# 80_LED_WS2812_panels.net
KiCad netlist of a schematic drawn in EAGLE
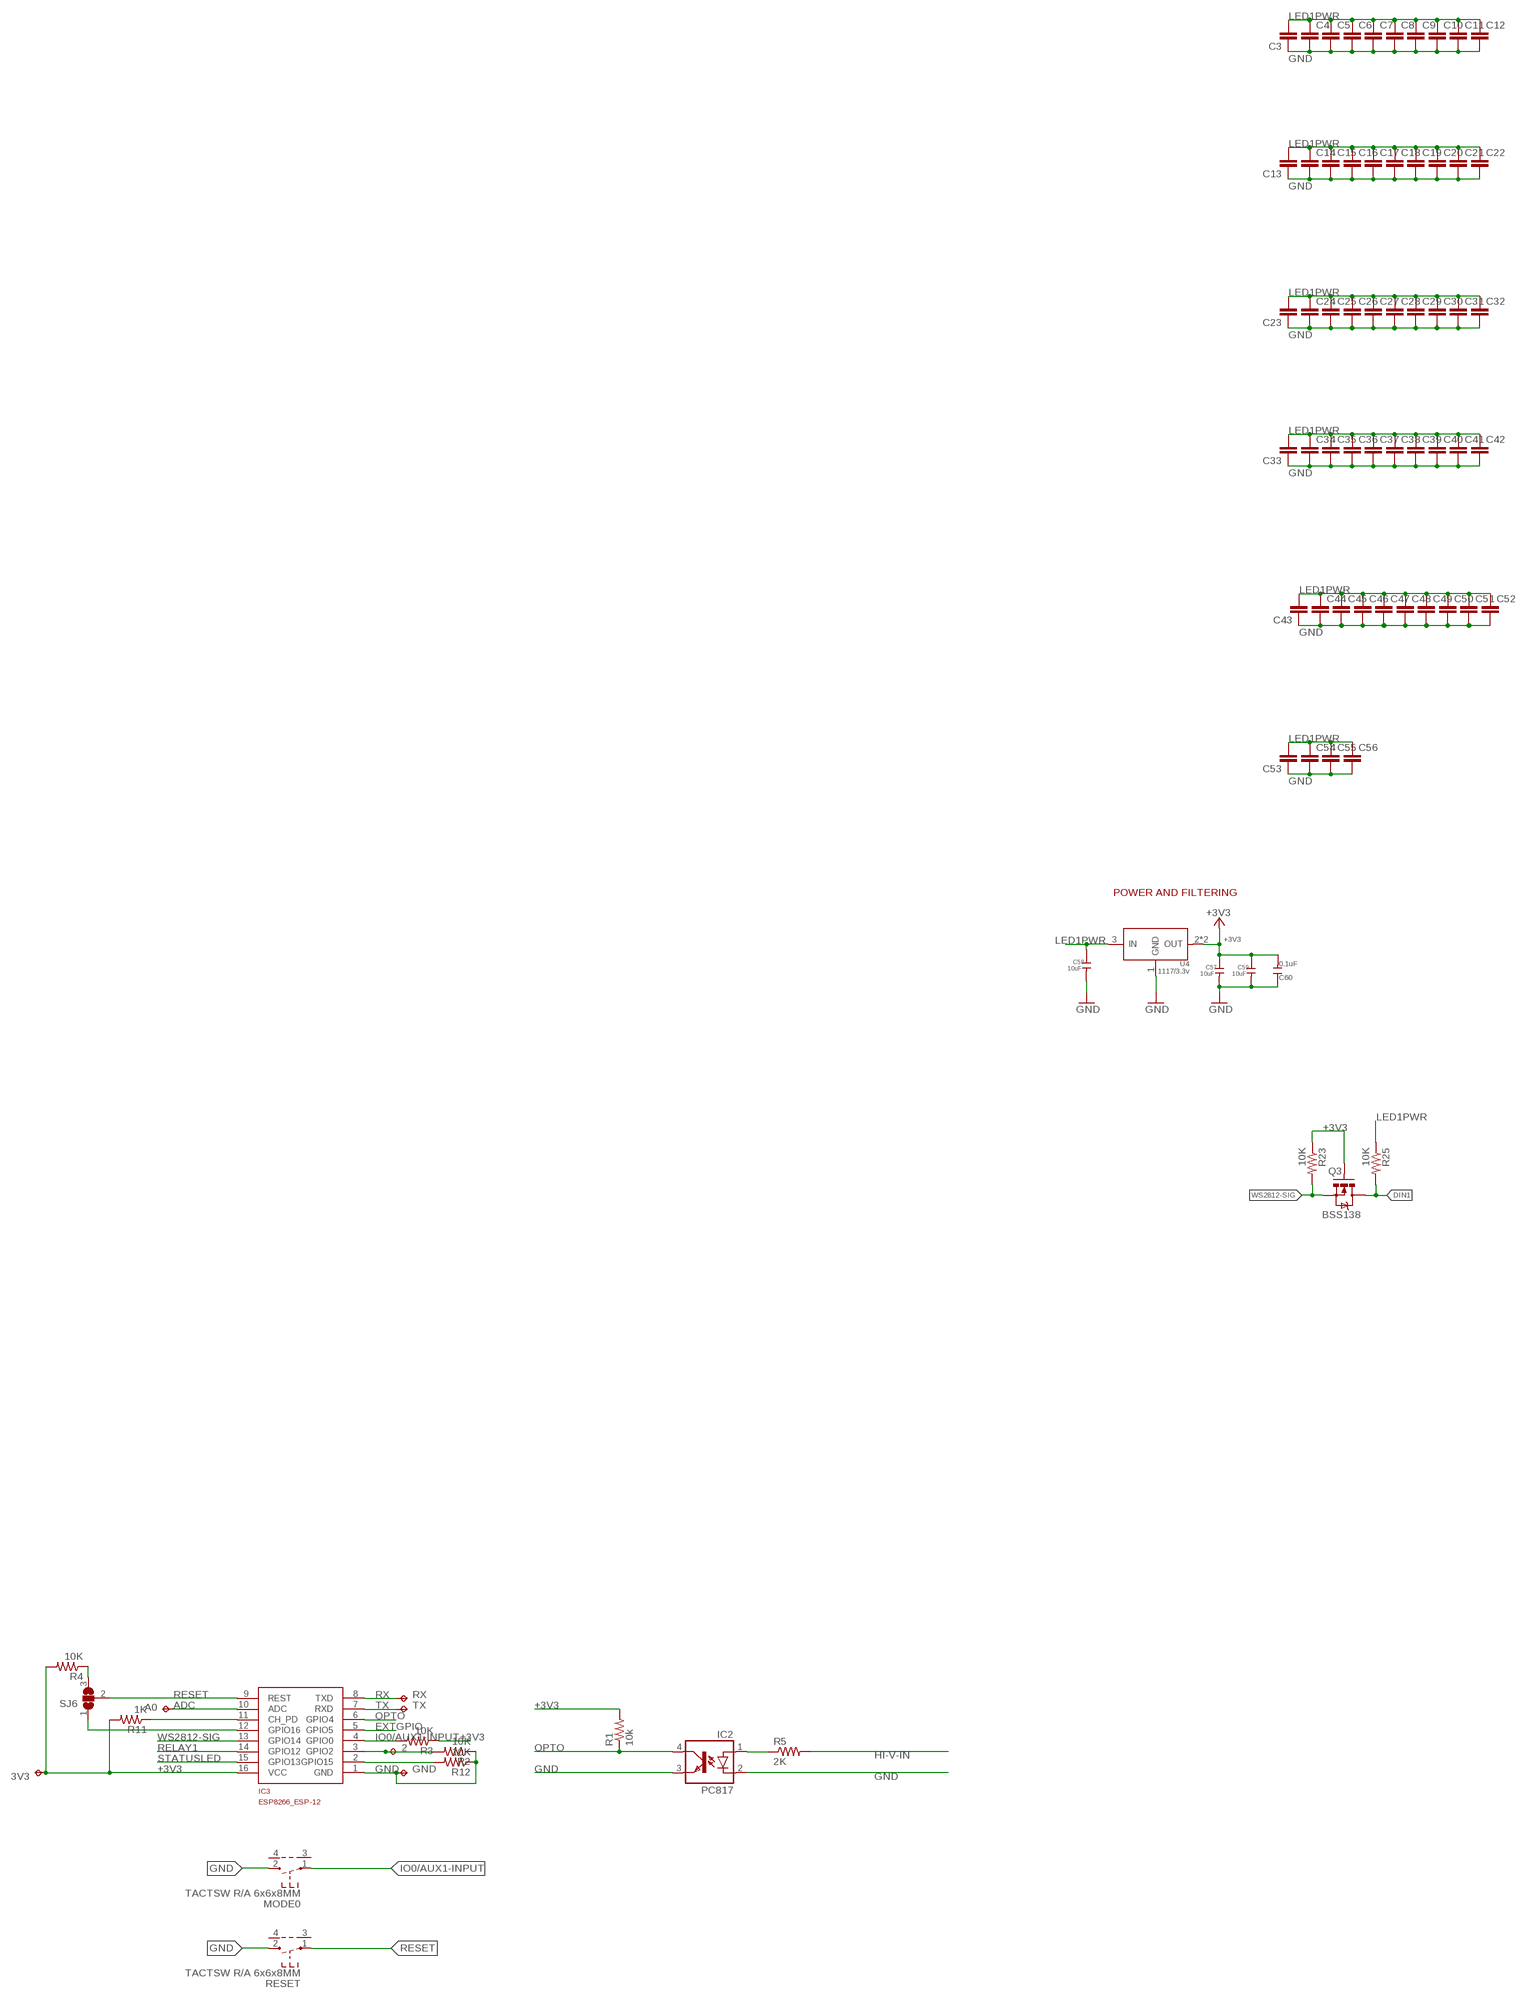
[diagram p0: schematic, sheet 1, part 1 of 2]
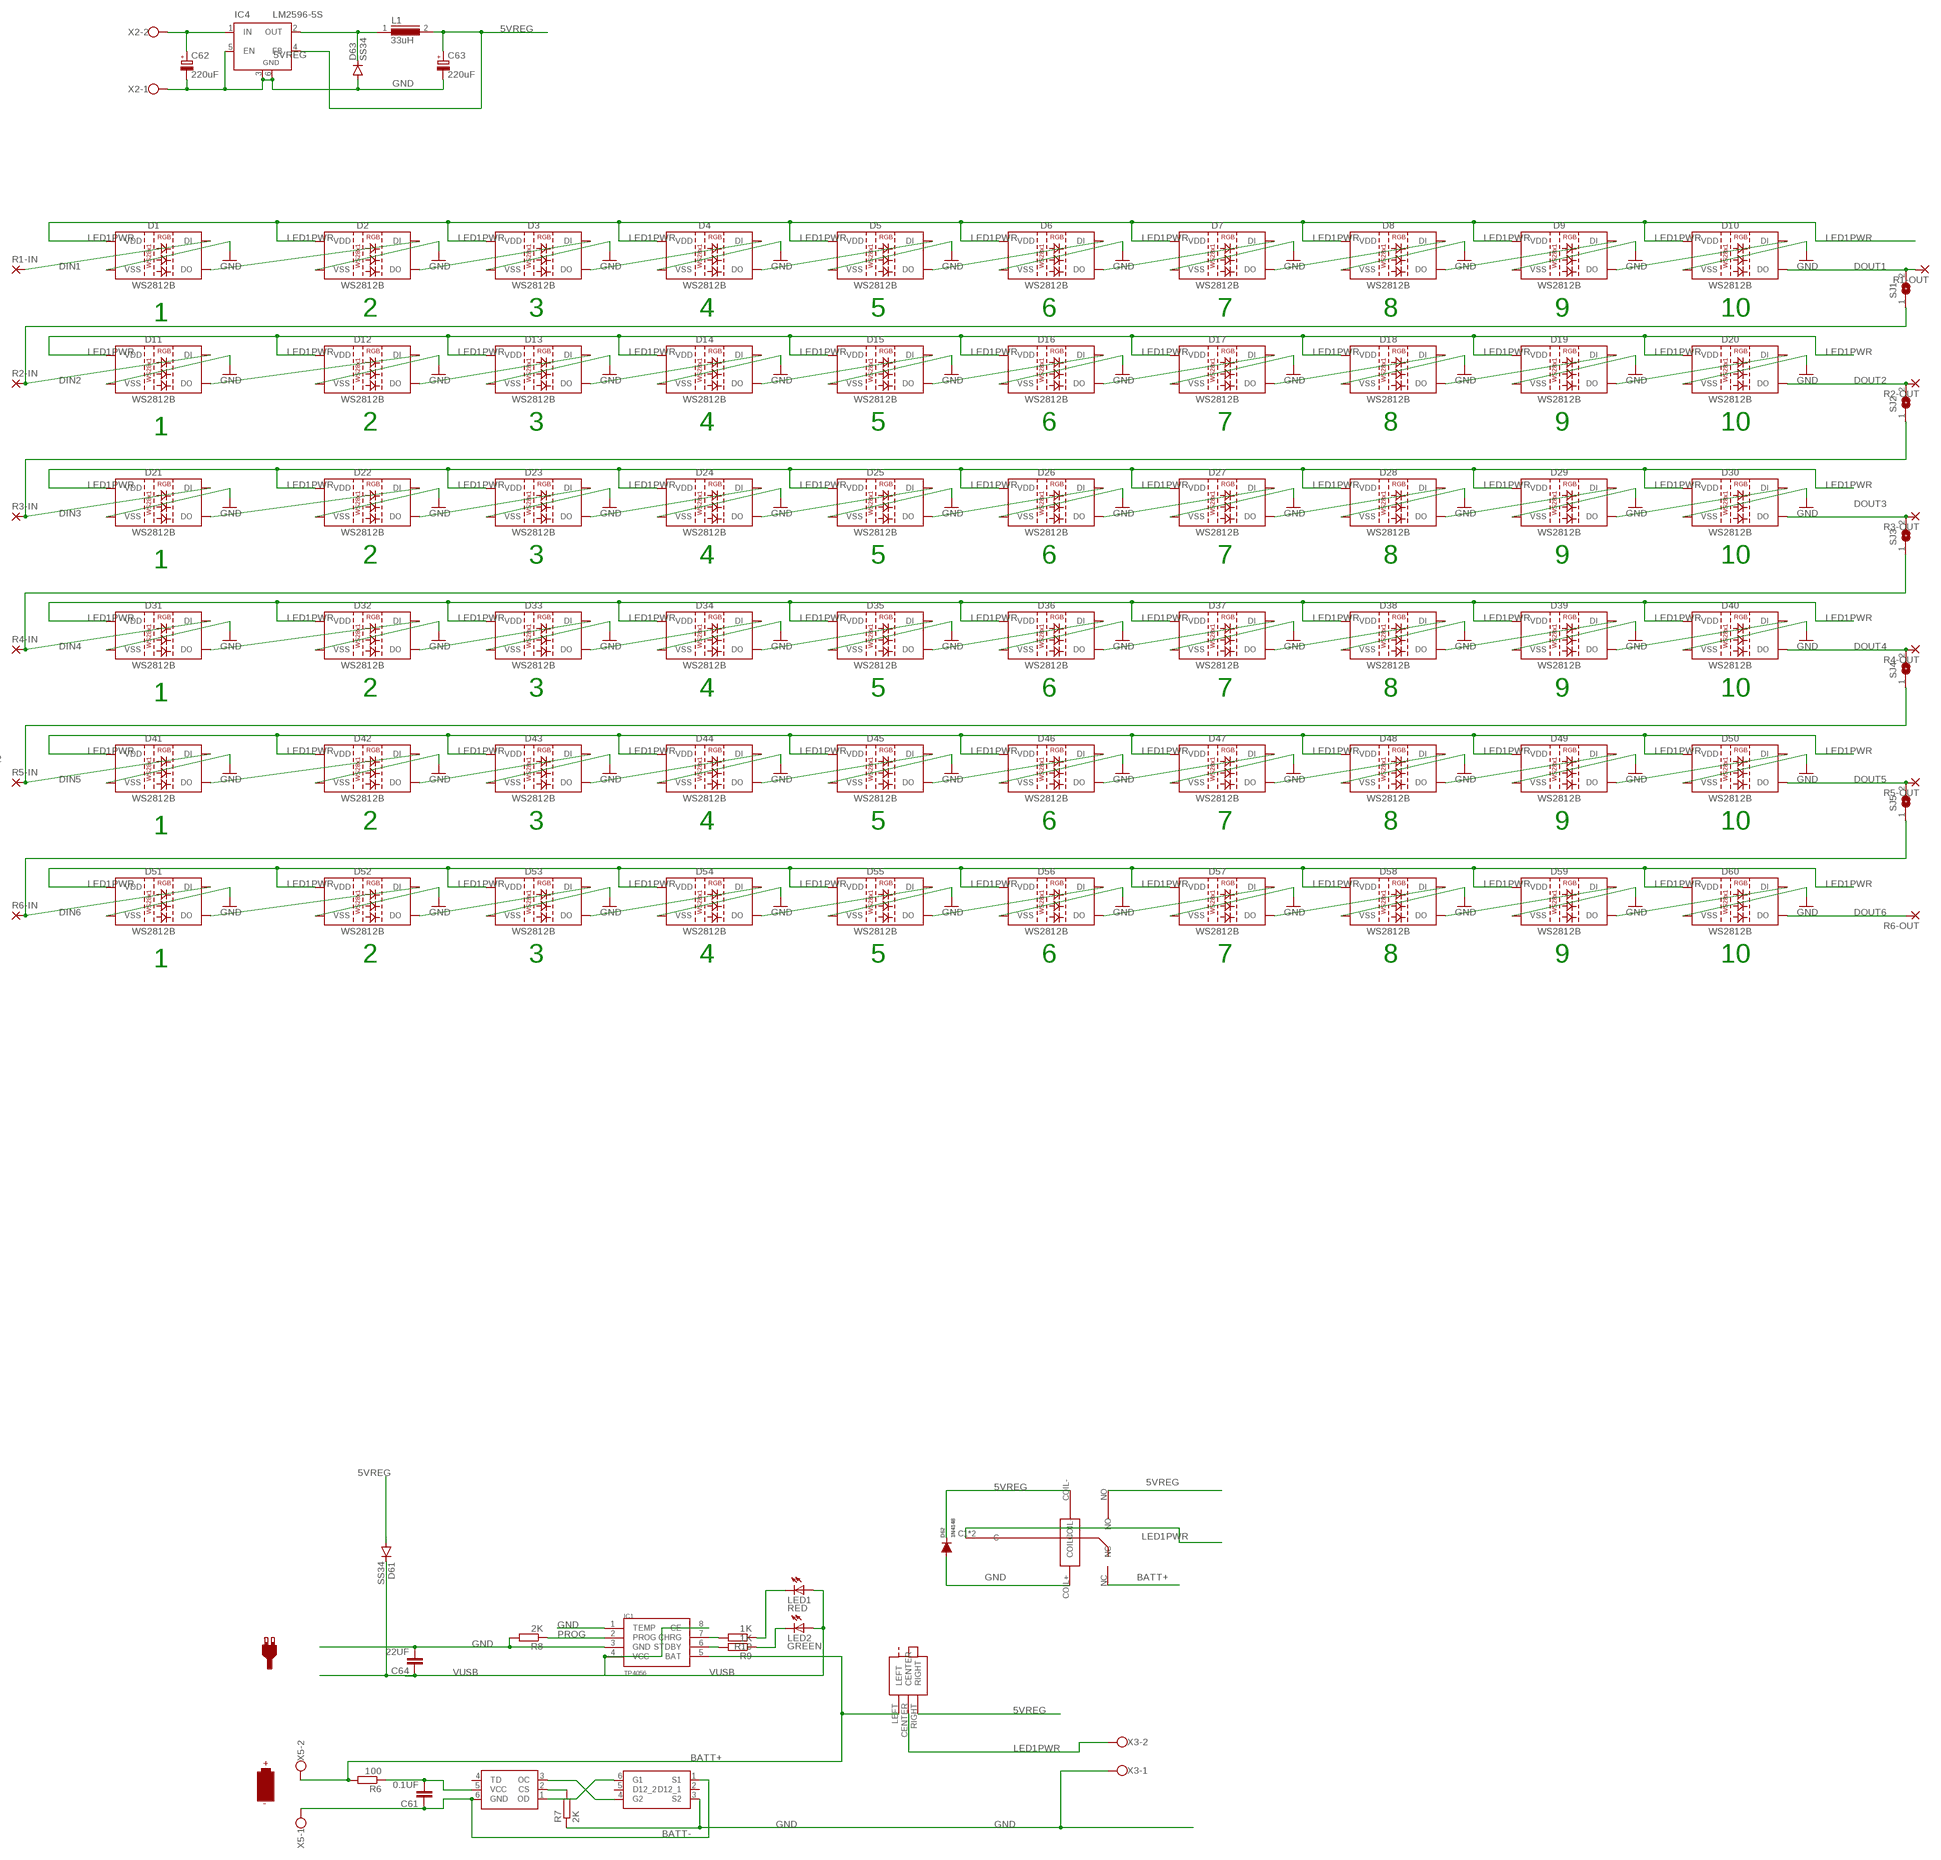
[diagram p1: schematic, sheet 1, part 2 of 2]

(export (version "E")
  (design (tool "Eeschema 10.0.6"))
  (components
    (comp (ref "2")
      (value "TPTP13SQ")
      (footprint "eagle-import:TP13SQ")
      (libsource (lib "eagle-import") (part "TPTP13SQ"))
    )
    (comp (ref "3V3")
      (value "TPTP13SQ")
      (footprint "eagle-import:TP13SQ")
      (libsource (lib "eagle-import") (part "TPTP13SQ"))
    )
    (comp (ref "A0")
      (value "TPTP13SQ")
      (footprint "eagle-import:TP13SQ")
      (libsource (lib "eagle-import") (part "TPTP13SQ"))
    )
    (comp (ref "C3")
      (value "C-EUC1206")
      (footprint "eagle-import:C1206@1")
      (libsource (lib "eagle-import") (part "C-EUC1206"))
    )
    (comp (ref "C4")
      (value "C-EUC1206")
      (footprint "eagle-import:C1206@1")
      (libsource (lib "eagle-import") (part "C-EUC1206"))
    )
    (comp (ref "C5")
      (value "C-EUC1206")
      (footprint "eagle-import:C1206@1")
      (libsource (lib "eagle-import") (part "C-EUC1206"))
    )
    (comp (ref "C6")
      (value "C-EUC1206")
      (footprint "eagle-import:C1206@1")
      (libsource (lib "eagle-import") (part "C-EUC1206"))
    )
    (comp (ref "C7")
      (value "C-EUC1206")
      (footprint "eagle-import:C1206@1")
      (libsource (lib "eagle-import") (part "C-EUC1206"))
    )
    (comp (ref "C8")
      (value "C-EUC1206")
      (footprint "eagle-import:C1206@1")
      (libsource (lib "eagle-import") (part "C-EUC1206"))
    )
    (comp (ref "C9")
      (value "C-EUC1206")
      (footprint "eagle-import:C1206@1")
      (libsource (lib "eagle-import") (part "C-EUC1206"))
    )
    (comp (ref "C10")
      (value "C-EUC1206")
      (footprint "eagle-import:C1206@1")
      (libsource (lib "eagle-import") (part "C-EUC1206"))
    )
    (comp (ref "C11")
      (value "C-EUC1206")
      (footprint "eagle-import:C1206@1")
      (libsource (lib "eagle-import") (part "C-EUC1206"))
    )
    (comp (ref "C12")
      (value "C-EUC1206")
      (footprint "eagle-import:C1206@1")
      (libsource (lib "eagle-import") (part "C-EUC1206"))
    )
    (comp (ref "C13")
      (value "C-EUC1206")
      (footprint "eagle-import:C1206@1")
      (libsource (lib "eagle-import") (part "C-EUC1206"))
    )
    (comp (ref "C14")
      (value "C-EUC1206")
      (footprint "eagle-import:C1206@1")
      (libsource (lib "eagle-import") (part "C-EUC1206"))
    )
    (comp (ref "C15")
      (value "C-EUC1206")
      (footprint "eagle-import:C1206@1")
      (libsource (lib "eagle-import") (part "C-EUC1206"))
    )
    (comp (ref "C16")
      (value "C-EUC1206")
      (footprint "eagle-import:C1206@1")
      (libsource (lib "eagle-import") (part "C-EUC1206"))
    )
    (comp (ref "C17")
      (value "C-EUC1206")
      (footprint "eagle-import:C1206@1")
      (libsource (lib "eagle-import") (part "C-EUC1206"))
    )
    (comp (ref "C18")
      (value "C-EUC1206")
      (footprint "eagle-import:C1206@1")
      (libsource (lib "eagle-import") (part "C-EUC1206"))
    )
    (comp (ref "C19")
      (value "C-EUC1206")
      (footprint "eagle-import:C1206@1")
      (libsource (lib "eagle-import") (part "C-EUC1206"))
    )
    (comp (ref "C20")
      (value "C-EUC1206")
      (footprint "eagle-import:C1206@1")
      (libsource (lib "eagle-import") (part "C-EUC1206"))
    )
    (comp (ref "C21")
      (value "C-EUC1206")
      (footprint "eagle-import:C1206@1")
      (libsource (lib "eagle-import") (part "C-EUC1206"))
    )
    (comp (ref "C22")
      (value "C-EUC1206")
      (footprint "eagle-import:C1206@1")
      (libsource (lib "eagle-import") (part "C-EUC1206"))
    )
    (comp (ref "C23")
      (value "C-EUC1206")
      (footprint "eagle-import:C1206@1")
      (libsource (lib "eagle-import") (part "C-EUC1206"))
    )
    (comp (ref "C24")
      (value "C-EUC1206")
      (footprint "eagle-import:C1206@1")
      (libsource (lib "eagle-import") (part "C-EUC1206"))
    )
    (comp (ref "C25")
      (value "C-EUC1206")
      (footprint "eagle-import:C1206@1")
      (libsource (lib "eagle-import") (part "C-EUC1206"))
    )
    (comp (ref "C26")
      (value "C-EUC1206")
      (footprint "eagle-import:C1206@1")
      (libsource (lib "eagle-import") (part "C-EUC1206"))
    )
    (comp (ref "C27")
      (value "C-EUC1206")
      (footprint "eagle-import:C1206@1")
      (libsource (lib "eagle-import") (part "C-EUC1206"))
    )
    (comp (ref "C28")
      (value "C-EUC1206")
      (footprint "eagle-import:C1206@1")
      (libsource (lib "eagle-import") (part "C-EUC1206"))
    )
    (comp (ref "C29")
      (value "C-EUC1206")
      (footprint "eagle-import:C1206@1")
      (libsource (lib "eagle-import") (part "C-EUC1206"))
    )
    (comp (ref "C30")
      (value "C-EUC1206")
      (footprint "eagle-import:C1206@1")
      (libsource (lib "eagle-import") (part "C-EUC1206"))
    )
    (comp (ref "C31")
      (value "C-EUC1206")
      (footprint "eagle-import:C1206@1")
      (libsource (lib "eagle-import") (part "C-EUC1206"))
    )
    (comp (ref "C32")
      (value "C-EUC1206")
      (footprint "eagle-import:C1206@1")
      (libsource (lib "eagle-import") (part "C-EUC1206"))
    )
    (comp (ref "C33")
      (value "C-EUC1206")
      (footprint "eagle-import:C1206@1")
      (libsource (lib "eagle-import") (part "C-EUC1206"))
    )
    (comp (ref "C34")
      (value "C-EUC1206")
      (footprint "eagle-import:C1206@1")
      (libsource (lib "eagle-import") (part "C-EUC1206"))
    )
    (comp (ref "C35")
      (value "C-EUC1206")
      (footprint "eagle-import:C1206@1")
      (libsource (lib "eagle-import") (part "C-EUC1206"))
    )
    (comp (ref "C36")
      (value "C-EUC1206")
      (footprint "eagle-import:C1206@1")
      (libsource (lib "eagle-import") (part "C-EUC1206"))
    )
    (comp (ref "C37")
      (value "C-EUC1206")
      (footprint "eagle-import:C1206@1")
      (libsource (lib "eagle-import") (part "C-EUC1206"))
    )
    (comp (ref "C38")
      (value "C-EUC1206")
      (footprint "eagle-import:C1206@1")
      (libsource (lib "eagle-import") (part "C-EUC1206"))
    )
    (comp (ref "C39")
      (value "C-EUC1206")
      (footprint "eagle-import:C1206@1")
      (libsource (lib "eagle-import") (part "C-EUC1206"))
    )
    (comp (ref "C40")
      (value "C-EUC1206")
      (footprint "eagle-import:C1206@1")
      (libsource (lib "eagle-import") (part "C-EUC1206"))
    )
    (comp (ref "C41")
      (value "C-EUC1206")
      (footprint "eagle-import:C1206@1")
      (libsource (lib "eagle-import") (part "C-EUC1206"))
    )
    (comp (ref "C42")
      (value "C-EUC1206")
      (footprint "eagle-import:C1206@1")
      (libsource (lib "eagle-import") (part "C-EUC1206"))
    )
    (comp (ref "C43")
      (value "C-EUC1206")
      (footprint "eagle-import:C1206@1")
      (libsource (lib "eagle-import") (part "C-EUC1206"))
    )
    (comp (ref "C44")
      (value "C-EUC1206")
      (footprint "eagle-import:C1206@1")
      (libsource (lib "eagle-import") (part "C-EUC1206"))
    )
    (comp (ref "C45")
      (value "C-EUC1206")
      (footprint "eagle-import:C1206@1")
      (libsource (lib "eagle-import") (part "C-EUC1206"))
    )
    (comp (ref "C46")
      (value "C-EUC1206")
      (footprint "eagle-import:C1206@1")
      (libsource (lib "eagle-import") (part "C-EUC1206"))
    )
    (comp (ref "C47")
      (value "C-EUC1206")
      (footprint "eagle-import:C1206@1")
      (libsource (lib "eagle-import") (part "C-EUC1206"))
    )
    (comp (ref "C48")
      (value "C-EUC1206")
      (footprint "eagle-import:C1206@1")
      (libsource (lib "eagle-import") (part "C-EUC1206"))
    )
    (comp (ref "C49")
      (value "C-EUC1206")
      (footprint "eagle-import:C1206@1")
      (libsource (lib "eagle-import") (part "C-EUC1206"))
    )
    (comp (ref "C50")
      (value "C-EUC1206")
      (footprint "eagle-import:C1206@1")
      (libsource (lib "eagle-import") (part "C-EUC1206"))
    )
    (comp (ref "C51")
      (value "C-EUC1206")
      (footprint "eagle-import:C1206@1")
      (libsource (lib "eagle-import") (part "C-EUC1206"))
    )
    (comp (ref "C52")
      (value "C-EUC1206")
      (footprint "eagle-import:C1206@1")
      (libsource (lib "eagle-import") (part "C-EUC1206"))
    )
    (comp (ref "C53")
      (value "C-EUC1206")
      (footprint "eagle-import:C1206@1")
      (libsource (lib "eagle-import") (part "C-EUC1206"))
    )
    (comp (ref "C54")
      (value "C-EUC1206")
      (footprint "eagle-import:C1206@1")
      (libsource (lib "eagle-import") (part "C-EUC1206"))
    )
    (comp (ref "C55")
      (value "C-EUC1206")
      (footprint "eagle-import:C1206@1")
      (libsource (lib "eagle-import") (part "C-EUC1206"))
    )
    (comp (ref "C56")
      (value "C-EUC1206")
      (footprint "eagle-import:C1206@1")
      (libsource (lib "eagle-import") (part "C-EUC1206"))
    )
    (comp (ref "C57")
      (value "10uF")
      (footprint "eagle-import:C1206")
      (libsource (lib "eagle-import") (part "C-1206"))
    )
    (comp (ref "C58")
      (value "10uF")
      (footprint "eagle-import:C1206")
      (libsource (lib "eagle-import") (part "C-1206"))
    )
    (comp (ref "C59")
      (value "10uF")
      (footprint "eagle-import:C1206")
      (libsource (lib "eagle-import") (part "C-1206"))
    )
    (comp (ref "C60")
      (value "0.1uF")
      (footprint "eagle-import:DISCRETE_C1206")
      (libsource (lib "eagle-import") (part "DISCRETE_C-1206"))
    )
    (comp (ref "C61")
      (value "0.1UF")
      (footprint "eagle-import:C1206@1")
      (libsource (lib "eagle-import") (part "C-EUC1206"))
    )
    (comp (ref "C62")
      (value "220uF")
      (footprint "eagle-import:E3,5-10")
      (libsource (lib "eagle-import") (part "CPOL-EUE3.5-10"))
    )
    (comp (ref "C63")
      (value "220uF")
      (footprint "eagle-import:E3,5-10")
      (libsource (lib "eagle-import") (part "CPOL-EUE3.5-10"))
    )
    (comp (ref "C64")
      (value "22UF")
      (footprint "eagle-import:C1812K@1")
      (libsource (lib "eagle-import") (part "C-EUC1812K"))
    )
    (comp (ref "D1")
      (value "WS2812B")
      (footprint "eagle-import:WS2812B")
      (libsource (lib "eagle-import") (part "WS2812B"))
    )
    (comp (ref "D2")
      (value "WS2812B")
      (footprint "eagle-import:WS2812B")
      (libsource (lib "eagle-import") (part "WS2812B"))
    )
    (comp (ref "D3")
      (value "WS2812B")
      (footprint "eagle-import:WS2812B")
      (libsource (lib "eagle-import") (part "WS2812B"))
    )
    (comp (ref "D4")
      (value "WS2812B")
      (footprint "eagle-import:WS2812B")
      (libsource (lib "eagle-import") (part "WS2812B"))
    )
    (comp (ref "D5")
      (value "WS2812B")
      (footprint "eagle-import:WS2812B")
      (libsource (lib "eagle-import") (part "WS2812B"))
    )
    (comp (ref "D6")
      (value "WS2812B")
      (footprint "eagle-import:WS2812B")
      (libsource (lib "eagle-import") (part "WS2812B"))
    )
    (comp (ref "D7")
      (value "WS2812B")
      (footprint "eagle-import:WS2812B")
      (libsource (lib "eagle-import") (part "WS2812B"))
    )
    (comp (ref "D8")
      (value "WS2812B")
      (footprint "eagle-import:WS2812B")
      (libsource (lib "eagle-import") (part "WS2812B"))
    )
    (comp (ref "D9")
      (value "WS2812B")
      (footprint "eagle-import:WS2812B")
      (libsource (lib "eagle-import") (part "WS2812B"))
    )
    (comp (ref "D10")
      (value "WS2812B")
      (footprint "eagle-import:WS2812B")
      (libsource (lib "eagle-import") (part "WS2812B"))
    )
    (comp (ref "D11")
      (value "WS2812B")
      (footprint "eagle-import:WS2812B")
      (libsource (lib "eagle-import") (part "WS2812B"))
    )
    (comp (ref "D12")
      (value "WS2812B")
      (footprint "eagle-import:WS2812B")
      (libsource (lib "eagle-import") (part "WS2812B"))
    )
    (comp (ref "D13")
      (value "WS2812B")
      (footprint "eagle-import:WS2812B")
      (libsource (lib "eagle-import") (part "WS2812B"))
    )
    (comp (ref "D14")
      (value "WS2812B")
      (footprint "eagle-import:WS2812B")
      (libsource (lib "eagle-import") (part "WS2812B"))
    )
    (comp (ref "D15")
      (value "WS2812B")
      (footprint "eagle-import:WS2812B")
      (libsource (lib "eagle-import") (part "WS2812B"))
    )
    (comp (ref "D16")
      (value "WS2812B")
      (footprint "eagle-import:WS2812B")
      (libsource (lib "eagle-import") (part "WS2812B"))
    )
    (comp (ref "D17")
      (value "WS2812B")
      (footprint "eagle-import:WS2812B")
      (libsource (lib "eagle-import") (part "WS2812B"))
    )
    (comp (ref "D18")
      (value "WS2812B")
      (footprint "eagle-import:WS2812B")
      (libsource (lib "eagle-import") (part "WS2812B"))
    )
    (comp (ref "D19")
      (value "WS2812B")
      (footprint "eagle-import:WS2812B")
      (libsource (lib "eagle-import") (part "WS2812B"))
    )
    (comp (ref "D20")
      (value "WS2812B")
      (footprint "eagle-import:WS2812B")
      (libsource (lib "eagle-import") (part "WS2812B"))
    )
    (comp (ref "D21")
      (value "WS2812B")
      (footprint "eagle-import:WS2812B")
      (libsource (lib "eagle-import") (part "WS2812B"))
    )
    (comp (ref "D22")
      (value "WS2812B")
      (footprint "eagle-import:WS2812B")
      (libsource (lib "eagle-import") (part "WS2812B"))
    )
    (comp (ref "D23")
      (value "WS2812B")
      (footprint "eagle-import:WS2812B")
      (libsource (lib "eagle-import") (part "WS2812B"))
    )
    (comp (ref "D24")
      (value "WS2812B")
      (footprint "eagle-import:WS2812B")
      (libsource (lib "eagle-import") (part "WS2812B"))
    )
    (comp (ref "D25")
      (value "WS2812B")
      (footprint "eagle-import:WS2812B")
      (libsource (lib "eagle-import") (part "WS2812B"))
    )
    (comp (ref "D26")
      (value "WS2812B")
      (footprint "eagle-import:WS2812B")
      (libsource (lib "eagle-import") (part "WS2812B"))
    )
    (comp (ref "D27")
      (value "WS2812B")
      (footprint "eagle-import:WS2812B")
      (libsource (lib "eagle-import") (part "WS2812B"))
    )
    (comp (ref "D28")
      (value "WS2812B")
      (footprint "eagle-import:WS2812B")
      (libsource (lib "eagle-import") (part "WS2812B"))
    )
    (comp (ref "D29")
      (value "WS2812B")
      (footprint "eagle-import:WS2812B")
      (libsource (lib "eagle-import") (part "WS2812B"))
    )
    (comp (ref "D30")
      (value "WS2812B")
      (footprint "eagle-import:WS2812B")
      (libsource (lib "eagle-import") (part "WS2812B"))
    )
    (comp (ref "D31")
      (value "WS2812B")
      (footprint "eagle-import:WS2812B")
      (libsource (lib "eagle-import") (part "WS2812B"))
    )
    (comp (ref "D32")
      (value "WS2812B")
      (footprint "eagle-import:WS2812B")
      (libsource (lib "eagle-import") (part "WS2812B"))
    )
    (comp (ref "D33")
      (value "WS2812B")
      (footprint "eagle-import:WS2812B")
      (libsource (lib "eagle-import") (part "WS2812B"))
    )
    (comp (ref "D34")
      (value "WS2812B")
      (footprint "eagle-import:WS2812B")
      (libsource (lib "eagle-import") (part "WS2812B"))
    )
    (comp (ref "D35")
      (value "WS2812B")
      (footprint "eagle-import:WS2812B")
      (libsource (lib "eagle-import") (part "WS2812B"))
    )
    (comp (ref "D36")
      (value "WS2812B")
      (footprint "eagle-import:WS2812B")
      (libsource (lib "eagle-import") (part "WS2812B"))
    )
    (comp (ref "D37")
      (value "WS2812B")
      (footprint "eagle-import:WS2812B")
      (libsource (lib "eagle-import") (part "WS2812B"))
    )
    (comp (ref "D38")
      (value "WS2812B")
      (footprint "eagle-import:WS2812B")
      (libsource (lib "eagle-import") (part "WS2812B"))
    )
    (comp (ref "D39")
      (value "WS2812B")
      (footprint "eagle-import:WS2812B")
      (libsource (lib "eagle-import") (part "WS2812B"))
    )
    (comp (ref "D40")
      (value "WS2812B")
      (footprint "eagle-import:WS2812B")
      (libsource (lib "eagle-import") (part "WS2812B"))
    )
    (comp (ref "D41")
      (value "WS2812B")
      (footprint "eagle-import:WS2812B")
      (libsource (lib "eagle-import") (part "WS2812B"))
    )
    (comp (ref "D42")
      (value "WS2812B")
      (footprint "eagle-import:WS2812B")
      (libsource (lib "eagle-import") (part "WS2812B"))
    )
    (comp (ref "D43")
      (value "WS2812B")
      (footprint "eagle-import:WS2812B")
      (libsource (lib "eagle-import") (part "WS2812B"))
    )
    (comp (ref "D44")
      (value "WS2812B")
      (footprint "eagle-import:WS2812B")
      (libsource (lib "eagle-import") (part "WS2812B"))
    )
    (comp (ref "D45")
      (value "WS2812B")
      (footprint "eagle-import:WS2812B")
      (libsource (lib "eagle-import") (part "WS2812B"))
    )
    (comp (ref "D46")
      (value "WS2812B")
      (footprint "eagle-import:WS2812B")
      (libsource (lib "eagle-import") (part "WS2812B"))
    )
    (comp (ref "D47")
      (value "WS2812B")
      (footprint "eagle-import:WS2812B")
      (libsource (lib "eagle-import") (part "WS2812B"))
    )
    (comp (ref "D48")
      (value "WS2812B")
      (footprint "eagle-import:WS2812B")
      (libsource (lib "eagle-import") (part "WS2812B"))
    )
    (comp (ref "D49")
      (value "WS2812B")
      (footprint "eagle-import:WS2812B")
      (libsource (lib "eagle-import") (part "WS2812B"))
    )
    (comp (ref "D50")
      (value "WS2812B")
      (footprint "eagle-import:WS2812B")
      (libsource (lib "eagle-import") (part "WS2812B"))
    )
    (comp (ref "D51")
      (value "WS2812B")
      (footprint "eagle-import:WS2812B")
      (libsource (lib "eagle-import") (part "WS2812B"))
    )
    (comp (ref "D52")
      (value "WS2812B")
      (footprint "eagle-import:WS2812B")
      (libsource (lib "eagle-import") (part "WS2812B"))
    )
    (comp (ref "D53")
      (value "WS2812B")
      (footprint "eagle-import:WS2812B")
      (libsource (lib "eagle-import") (part "WS2812B"))
    )
    (comp (ref "D54")
      (value "WS2812B")
      (footprint "eagle-import:WS2812B")
      (libsource (lib "eagle-import") (part "WS2812B"))
    )
    (comp (ref "D55")
      (value "WS2812B")
      (footprint "eagle-import:WS2812B")
      (libsource (lib "eagle-import") (part "WS2812B"))
    )
    (comp (ref "D56")
      (value "WS2812B")
      (footprint "eagle-import:WS2812B")
      (libsource (lib "eagle-import") (part "WS2812B"))
    )
    (comp (ref "D57")
      (value "WS2812B")
      (footprint "eagle-import:WS2812B")
      (libsource (lib "eagle-import") (part "WS2812B"))
    )
    (comp (ref "D58")
      (value "WS2812B")
      (footprint "eagle-import:WS2812B")
      (libsource (lib "eagle-import") (part "WS2812B"))
    )
    (comp (ref "D59")
      (value "WS2812B")
      (footprint "eagle-import:WS2812B")
      (libsource (lib "eagle-import") (part "WS2812B"))
    )
    (comp (ref "D60")
      (value "WS2812B")
      (footprint "eagle-import:WS2812B")
      (libsource (lib "eagle-import") (part "WS2812B"))
    )
    (comp (ref "D61")
      (value "SS34")
      (footprint "eagle-import:DO-214AC")
      (libsource (lib "eagle-import") (part "DIODE-DO-214AC"))
    )
    (comp (ref "D62")
      (value "1N4148")
      (footprint "eagle-import:SOD-323")
      (libsource (lib "eagle-import") (part "DIODE-BAS16J"))
    )
    (comp (ref "D63")
      (value "SS34")
      (footprint "eagle-import:DO-214AC")
      (libsource (lib "eagle-import") (part "DIODE-DO-214AC"))
    )
    (comp (ref "GND")
      (value "TPTP13SQ")
      (footprint "eagle-import:TP13SQ")
      (libsource (lib "eagle-import") (part "TPTP13SQ"))
    )
    (comp (ref "IC1")
      (value "TP4056")
      (footprint "eagle-import:SOP-8")
      (libsource (lib "eagle-import") (part "TP4056"))
    )
    (comp (ref "IC2")
      (value "PC817")
      (footprint "eagle-import:DIL04")
      (fields (field (name "MPN") "PC817X4J000F"))
      (libsource (lib "eagle-import") (part "PC817"))
    )
    (comp (ref "IC3")
      (value "ESP8266_ESP-12")
      (footprint "eagle-import:ESP8266-ESP12")
      (libsource (lib "eagle-import") (part "ESP8266_ESP-12"))
    )
    (comp (ref "IC4")
      (value "LM2596-5S")
      (footprint "eagle-import:TO263-5")
      (libsource (lib "eagle-import") (part "LM2596S"))
    )
    (comp (ref "L1")
      (value "33uH")
      (footprint "eagle-import:DR127")
      (libsource (lib "eagle-import") (part "DR127"))
    )
    (comp (ref "LED1")
      (value "RED")
      (footprint "eagle-import:LED3MM")
      (libsource (lib "eagle-import") (part "LED3MM"))
    )
    (comp (ref "LED2")
      (value "GREEN")
      (footprint "eagle-import:LED3MM")
      (libsource (lib "eagle-import") (part "LED3MM"))
    )
    (comp (ref "MODE0")
      (value "TACTSW R/A 6x6x8MM")
      (footprint "eagle-import:SW_TACT_STANDARD_RIGHT_ANGLE")
      (libsource (lib "eagle-import") (part "SW_TACT_4P_B"))
    )
    (comp (ref "Q3")
      (value "BSS138")
      (footprint "eagle-import:SOT23-3")
      (libsource (lib "eagle-import") (part "MOSFET-NCHANNELSMD"))
    )
    (comp (ref "R1")
      (value "10k")
      (footprint "eagle-import:R1206")
      (libsource (lib "eagle-import") (part "R-US_R1206"))
    )
    (comp (ref "R1-IN")
      (value "2,15/1,0")
      (footprint "eagle-import:2,15_1,0")
      (libsource (lib "eagle-import") (part "2,15/1,0"))
    )
    (comp (ref "R1-OUT")
      (value "2,15/1,0")
      (footprint "eagle-import:2,15_1,0")
      (libsource (lib "eagle-import") (part "2,15/1,0"))
    )
    (comp (ref "R2")
      (value "10K")
      (footprint "eagle-import:R1206")
      (libsource (lib "eagle-import") (part "R-US_R1206"))
    )
    (comp (ref "R2-IN")
      (value "2,15/1,0")
      (footprint "eagle-import:2,15_1,0")
      (libsource (lib "eagle-import") (part "2,15/1,0"))
    )
    (comp (ref "R2-OUT")
      (value "2,15/1,0")
      (footprint "eagle-import:2,15_1,0")
      (libsource (lib "eagle-import") (part "2,15/1,0"))
    )
    (comp (ref "R3")
      (value "10K")
      (footprint "eagle-import:R1206")
      (libsource (lib "eagle-import") (part "R-US_R1206"))
    )
    (comp (ref "R3-IN")
      (value "2,15/1,0")
      (footprint "eagle-import:2,15_1,0")
      (libsource (lib "eagle-import") (part "2,15/1,0"))
    )
    (comp (ref "R3-OUT")
      (value "2,15/1,0")
      (footprint "eagle-import:2,15_1,0")
      (libsource (lib "eagle-import") (part "2,15/1,0"))
    )
    (comp (ref "R4")
      (value "10K")
      (footprint "eagle-import:R1206")
      (libsource (lib "eagle-import") (part "R-US_R1206"))
    )
    (comp (ref "R4-IN")
      (value "2,15/1,0")
      (footprint "eagle-import:2,15_1,0")
      (libsource (lib "eagle-import") (part "2,15/1,0"))
    )
    (comp (ref "R4-OUT")
      (value "2,15/1,0")
      (footprint "eagle-import:2,15_1,0")
      (libsource (lib "eagle-import") (part "2,15/1,0"))
    )
    (comp (ref "R5")
      (value "2K")
      (footprint "eagle-import:R1206")
      (libsource (lib "eagle-import") (part "R-US_R1206"))
    )
    (comp (ref "R5-IN")
      (value "2,15/1,0")
      (footprint "eagle-import:2,15_1,0")
      (libsource (lib "eagle-import") (part "2,15/1,0"))
    )
    (comp (ref "R5-OUT")
      (value "2,15/1,0")
      (footprint "eagle-import:2,15_1,0")
      (libsource (lib "eagle-import") (part "2,15/1,0"))
    )
    (comp (ref "R6")
      (value "100")
      (footprint "eagle-import:R1206")
      (libsource (lib "eagle-import") (part "R-EU_R1206"))
    )
    (comp (ref "R6-IN")
      (value "2,15/1,0")
      (footprint "eagle-import:2,15_1,0")
      (libsource (lib "eagle-import") (part "2,15/1,0"))
    )
    (comp (ref "R6-OUT")
      (value "2,15/1,0")
      (footprint "eagle-import:2,15_1,0")
      (libsource (lib "eagle-import") (part "2,15/1,0"))
    )
    (comp (ref "R7")
      (value "2K")
      (footprint "eagle-import:R1206")
      (libsource (lib "eagle-import") (part "R-EU_R1206"))
    )
    (comp (ref "R8")
      (value "2K")
      (footprint "eagle-import:R1206")
      (libsource (lib "eagle-import") (part "R-EU_R1206"))
    )
    (comp (ref "R9")
      (value "1K")
      (footprint "eagle-import:R1206")
      (libsource (lib "eagle-import") (part "R-EU_R1206"))
    )
    (comp (ref "R10")
      (value "1K")
      (footprint "eagle-import:R1206")
      (libsource (lib "eagle-import") (part "R-EU_R1206"))
    )
    (comp (ref "R11")
      (value "1K")
      (footprint "eagle-import:R1206")
      (libsource (lib "eagle-import") (part "R-US_R1206"))
    )
    (comp (ref "R12")
      (value "10K")
      (footprint "eagle-import:R1206")
      (libsource (lib "eagle-import") (part "R-US_R1206"))
    )
    (comp (ref "R23")
      (value "10K")
      (footprint "eagle-import:1206")
      (libsource (lib "eagle-import") (part "RESISTOR1206"))
    )
    (comp (ref "R25")
      (value "10K")
      (footprint "eagle-import:1206")
      (libsource (lib "eagle-import") (part "RESISTOR1206"))
    )
    (comp (ref "RESET")
      (value "TACTSW R/A 6x6x8MM")
      (footprint "eagle-import:SW_TACT_STANDARD_RIGHT_ANGLE")
      (libsource (lib "eagle-import") (part "SW_TACT_4P_B"))
    )
    (comp (ref "RX")
      (value "TPTP13SQ")
      (footprint "eagle-import:TP13SQ")
      (libsource (lib "eagle-import") (part "TPTP13SQ"))
    )
    (comp (ref "SJ1") (value "SJ") (footprint "eagle-import:SJ") (libsource (lib "eagle-import") (part "SJ")))
    (comp (ref "SJ2") (value "SJ") (footprint "eagle-import:SJ") (libsource (lib "eagle-import") (part "SJ")))
    (comp (ref "SJ3") (value "SJ") (footprint "eagle-import:SJ") (libsource (lib "eagle-import") (part "SJ")))
    (comp (ref "SJ4") (value "SJ") (footprint "eagle-import:SJ") (libsource (lib "eagle-import") (part "SJ")))
    (comp (ref "SJ5") (value "SJ") (footprint "eagle-import:SJ") (libsource (lib "eagle-import") (part "SJ")))
    (comp (ref "SJ6")
      (value "SJ2W")
      (footprint "eagle-import:SJ_2")
      (libsource (lib "eagle-import") (part "SJ2W"))
    )
    (comp (ref "TX")
      (value "TPTP13SQ")
      (footprint "eagle-import:TP13SQ")
      (libsource (lib "eagle-import") (part "TPTP13SQ"))
    )
    (comp (ref "U$1")
      (value "FS312F-G")
      (footprint "eagle-import:SOT23-6")
      (libsource (lib "eagle-import") (part "FS312F-G"))
    )
    (comp (ref "U$2")
      (value "FS8205")
      (footprint "eagle-import:SOT23-6")
      (libsource (lib "eagle-import") (part "FS8205"))
    )
    (comp (ref "U$3")
      (value "XKBENTERPRISESS-12D11G5R")
      (footprint "eagle-import:XKBENTERPRISESS-12D11G5R")
      (libsource (lib "eagle-import") (part "XKBENTERPRISESS-12D11G5R"))
    )
    (comp (ref "U$13")
      (value "JRC-21F-4100")
      (footprint "eagle-import:JRC-21F-4100")
      (libsource (lib "eagle-import") (part "JRC-21F-4100"))
    )
    (comp (ref "U4")
      (value "1117/3.3v")
      (footprint "eagle-import:SOT-223")
      (libsource (lib "eagle-import") (part "LD1117S"))
    )
    (comp (ref "X2")
      (value "W237-102")
      (footprint "eagle-import:W237-102")
      (fields (field (name "MPN") "237-102"))
      (libsource (lib "eagle-import") (part "W237-102"))
    )
    (comp (ref "X3")
      (value "W237-102")
      (footprint "eagle-import:W237-102")
      (fields (field (name "MPN") "237-102"))
      (libsource (lib "eagle-import") (part "W237-102"))
    )
    (comp (ref "X5")
      (value "W237-102")
      (footprint "eagle-import:W237-102")
      (fields (field (name "MPN") "237-102"))
      (libsource (lib "eagle-import") (part "W237-102"))
    )
  )
  (nets
    (net (code "1") (name "+3V3") (class "Default")
      (node (ref "3V3") (pin "TP") (pinfunction "TP_TP") (pintype "input"))
      (node (ref "C57") (pin "1") (pinfunction "1_1") (pintype "passive"))
      (node (ref "C59") (pin "1") (pinfunction "1_1") (pintype "passive"))
      (node (ref "C60") (pin "2") (pinfunction "2_2") (pintype "passive"))
      (node (ref "IC3") (pin "16") (pinfunction "VCC_16") (pintype "bidirectional"))
      (node (ref "Q3") (pin "1") (pinfunction "G_1") (pintype "passive"))
      (node (ref "R1") (pin "2") (pinfunction "2_2") (pintype "passive"))
      (node (ref "R11") (pin "2") (pinfunction "2_2") (pintype "passive"))
      (node (ref "R23") (pin "1") (pinfunction "1_1") (pintype "passive"))
      (node (ref "R3") (pin "1") (pinfunction "1_1") (pintype "passive"))
      (node (ref "R4") (pin "2") (pinfunction "2_2") (pintype "passive"))
      (node (ref "U4") (pin "2") (pinfunction "OUT_2") (pintype "bidirectional"))
      (node (ref "U4") (pin "TER") (pinfunction "OUT_TER") (pintype "bidirectional"))
    )
    (net (code "2") (name "/5VREG") (class "Default")
      (node (ref "C63") (pin "+") (pinfunction "+_+") (pintype "passive"))
      (node (ref "D61") (pin "A") (pinfunction "A_A") (pintype "passive"))
      (node (ref "D62") (pin "C") (pinfunction "C_C") (pintype "passive"))
      (node (ref "IC4") (pin "4") (pinfunction "FB_4") (pintype "input"))
      (node (ref "L1") (pin "2") (pinfunction "2_2") (pintype "passive"))
      (node (ref "U$13") (pin "COIL-") (pinfunction "COIL-_COIL-") (pintype "bidirectional"))
      (node (ref "U$13") (pin "NO") (pinfunction "NO_NO") (pintype "bidirectional"))
      (node (ref "U$3") (pin "RIGHT") (pinfunction "RIGHT_RIGHT") (pintype "bidirectional"))
    )
    (net (code "3") (name "/ADC") (class "Default")
      (node (ref "A0") (pin "TP") (pinfunction "TP_TP") (pintype "input"))
      (node (ref "IC3") (pin "10") (pinfunction "ADC_10") (pintype "bidirectional"))
    )
    (net (code "4") (name "/BATT+") (class "Default")
      (node (ref "IC1") (pin "5") (pinfunction "BAT_5") (pintype "bidirectional"))
      (node (ref "R6") (pin "2") (pinfunction "2_2") (pintype "passive"))
      (node (ref "U$13") (pin "NC") (pinfunction "NC_NC") (pintype "bidirectional"))
      (node (ref "U$3") (pin "LEFT") (pinfunction "LEFT_LEFT") (pintype "bidirectional"))
      (node (ref "X5") (pin "2") (pinfunction "KL_2") (pintype "passive"))
    )
    (net (code "5") (name "/BATT-") (class "Default")
      (node (ref "C61") (pin "1") (pinfunction "1_1") (pintype "passive"))
      (node (ref "U$1") (pin "6") (pinfunction "GND_6") (pintype "bidirectional"))
      (node (ref "U$2") (pin "1") (pinfunction "S1_1") (pintype "bidirectional"))
      (node (ref "X5") (pin "1") (pinfunction "KL_1") (pintype "passive"))
    )
    (net (code "6") (name "/DIN2") (class "Default")
      (node (ref "D11") (pin "4") (pinfunction "DI_4") (pintype "bidirectional"))
      (node (ref "R2-IN") (pin "1") (pinfunction "P_1") (pintype "passive"))
      (node (ref "SJ1") (pin "1") (pinfunction "1_1") (pintype "passive"))
    )
    (net (code "7") (name "/DIN3") (class "Default")
      (node (ref "D21") (pin "4") (pinfunction "DI_4") (pintype "bidirectional"))
      (node (ref "R3-IN") (pin "1") (pinfunction "P_1") (pintype "passive"))
      (node (ref "SJ2") (pin "1") (pinfunction "1_1") (pintype "passive"))
    )
    (net (code "8") (name "/DIN4") (class "Default")
      (node (ref "D31") (pin "4") (pinfunction "DI_4") (pintype "bidirectional"))
      (node (ref "R4-IN") (pin "1") (pinfunction "P_1") (pintype "passive"))
      (node (ref "SJ3") (pin "1") (pinfunction "1_1") (pintype "passive"))
    )
    (net (code "9") (name "/DIN5") (class "Default")
      (node (ref "D41") (pin "4") (pinfunction "DI_4") (pintype "bidirectional"))
      (node (ref "R5-IN") (pin "1") (pinfunction "P_1") (pintype "passive"))
      (node (ref "SJ4") (pin "1") (pinfunction "1_1") (pintype "passive"))
    )
    (net (code "10") (name "/DIN6") (class "Default")
      (node (ref "D51") (pin "4") (pinfunction "DI_4") (pintype "bidirectional"))
      (node (ref "R6-IN") (pin "1") (pinfunction "P_1") (pintype "passive"))
      (node (ref "SJ5") (pin "1") (pinfunction "1_1") (pintype "passive"))
    )
    (net (code "11") (name "/DOUT1") (class "Default")
      (node (ref "D10") (pin "2") (pinfunction "DO_2") (pintype "bidirectional"))
      (node (ref "R1-OUT") (pin "1") (pinfunction "P_1") (pintype "passive"))
      (node (ref "SJ1") (pin "2") (pinfunction "2_2") (pintype "passive"))
    )
    (net (code "12") (name "/DOUT2") (class "Default")
      (node (ref "D20") (pin "2") (pinfunction "DO_2") (pintype "bidirectional"))
      (node (ref "R2-OUT") (pin "1") (pinfunction "P_1") (pintype "passive"))
      (node (ref "SJ2") (pin "2") (pinfunction "2_2") (pintype "passive"))
    )
    (net (code "13") (name "/DOUT3") (class "Default")
      (node (ref "D30") (pin "2") (pinfunction "DO_2") (pintype "bidirectional"))
      (node (ref "R3-OUT") (pin "1") (pinfunction "P_1") (pintype "passive"))
      (node (ref "SJ3") (pin "2") (pinfunction "2_2") (pintype "passive"))
    )
    (net (code "14") (name "/DOUT4") (class "Default")
      (node (ref "D40") (pin "2") (pinfunction "DO_2") (pintype "bidirectional"))
      (node (ref "R4-OUT") (pin "1") (pinfunction "P_1") (pintype "passive"))
      (node (ref "SJ4") (pin "2") (pinfunction "2_2") (pintype "passive"))
    )
    (net (code "15") (name "/DOUT5") (class "Default")
      (node (ref "D50") (pin "2") (pinfunction "DO_2") (pintype "bidirectional"))
      (node (ref "R5-OUT") (pin "1") (pinfunction "P_1") (pintype "passive"))
      (node (ref "SJ5") (pin "2") (pinfunction "2_2") (pintype "passive"))
    )
    (net (code "16") (name "/DOUT6") (class "Default")
      (node (ref "D60") (pin "2") (pinfunction "DO_2") (pintype "bidirectional"))
      (node (ref "R6-OUT") (pin "1") (pinfunction "P_1") (pintype "passive"))
    )
    (net (code "17") (name "/EXTGPIO") (class "Default")
      (node (ref "IC3") (pin "5") (pinfunction "GPIO5_5") (pintype "bidirectional"))
    )
    (net (code "18") (name "/HI-V-IN") (class "Default")
      (node (ref "C62") (pin "+") (pinfunction "+_+") (pintype "passive"))
      (node (ref "IC4") (pin "1") (pinfunction "IN_1") (pintype "input"))
      (node (ref "R5") (pin "2") (pinfunction "2_2") (pintype "passive"))
      (node (ref "X2") (pin "2") (pinfunction "KL_2") (pintype "passive"))
    )
    (net (code "19") (name "/LED1PWR") (class "Default")
      (node (ref "C10") (pin "1") (pinfunction "1_1") (pintype "passive"))
      (node (ref "C11") (pin "1") (pinfunction "1_1") (pintype "passive"))
      (node (ref "C12") (pin "1") (pinfunction "1_1") (pintype "passive"))
      (node (ref "C13") (pin "2") (pinfunction "2_2") (pintype "passive"))
      (node (ref "C14") (pin "1") (pinfunction "1_1") (pintype "passive"))
      (node (ref "C15") (pin "1") (pinfunction "1_1") (pintype "passive"))
      (node (ref "C16") (pin "1") (pinfunction "1_1") (pintype "passive"))
      (node (ref "C17") (pin "1") (pinfunction "1_1") (pintype "passive"))
      (node (ref "C18") (pin "1") (pinfunction "1_1") (pintype "passive"))
      (node (ref "C19") (pin "1") (pinfunction "1_1") (pintype "passive"))
      (node (ref "C20") (pin "1") (pinfunction "1_1") (pintype "passive"))
      (node (ref "C21") (pin "1") (pinfunction "1_1") (pintype "passive"))
      (node (ref "C22") (pin "1") (pinfunction "1_1") (pintype "passive"))
      (node (ref "C23") (pin "2") (pinfunction "2_2") (pintype "passive"))
      (node (ref "C24") (pin "1") (pinfunction "1_1") (pintype "passive"))
      (node (ref "C25") (pin "1") (pinfunction "1_1") (pintype "passive"))
      (node (ref "C26") (pin "1") (pinfunction "1_1") (pintype "passive"))
      (node (ref "C27") (pin "1") (pinfunction "1_1") (pintype "passive"))
      (node (ref "C28") (pin "1") (pinfunction "1_1") (pintype "passive"))
      (node (ref "C29") (pin "1") (pinfunction "1_1") (pintype "passive"))
      (node (ref "C3") (pin "2") (pinfunction "2_2") (pintype "passive"))
      (node (ref "C30") (pin "1") (pinfunction "1_1") (pintype "passive"))
      (node (ref "C31") (pin "1") (pinfunction "1_1") (pintype "passive"))
      (node (ref "C32") (pin "1") (pinfunction "1_1") (pintype "passive"))
      (node (ref "C33") (pin "2") (pinfunction "2_2") (pintype "passive"))
      (node (ref "C34") (pin "1") (pinfunction "1_1") (pintype "passive"))
      (node (ref "C35") (pin "1") (pinfunction "1_1") (pintype "passive"))
      (node (ref "C36") (pin "1") (pinfunction "1_1") (pintype "passive"))
      (node (ref "C37") (pin "1") (pinfunction "1_1") (pintype "passive"))
      (node (ref "C38") (pin "1") (pinfunction "1_1") (pintype "passive"))
      (node (ref "C39") (pin "1") (pinfunction "1_1") (pintype "passive"))
      (node (ref "C4") (pin "1") (pinfunction "1_1") (pintype "passive"))
      (node (ref "C40") (pin "1") (pinfunction "1_1") (pintype "passive"))
      (node (ref "C41") (pin "1") (pinfunction "1_1") (pintype "passive"))
      (node (ref "C42") (pin "1") (pinfunction "1_1") (pintype "passive"))
      (node (ref "C43") (pin "2") (pinfunction "2_2") (pintype "passive"))
      (node (ref "C44") (pin "1") (pinfunction "1_1") (pintype "passive"))
      (node (ref "C45") (pin "1") (pinfunction "1_1") (pintype "passive"))
      (node (ref "C46") (pin "1") (pinfunction "1_1") (pintype "passive"))
      (node (ref "C47") (pin "1") (pinfunction "1_1") (pintype "passive"))
      (node (ref "C48") (pin "1") (pinfunction "1_1") (pintype "passive"))
      (node (ref "C49") (pin "1") (pinfunction "1_1") (pintype "passive"))
      (node (ref "C5") (pin "1") (pinfunction "1_1") (pintype "passive"))
      (node (ref "C50") (pin "1") (pinfunction "1_1") (pintype "passive"))
      (node (ref "C51") (pin "1") (pinfunction "1_1") (pintype "passive"))
      (node (ref "C52") (pin "1") (pinfunction "1_1") (pintype "passive"))
      (node (ref "C53") (pin "2") (pinfunction "2_2") (pintype "passive"))
      (node (ref "C54") (pin "1") (pinfunction "1_1") (pintype "passive"))
      (node (ref "C55") (pin "1") (pinfunction "1_1") (pintype "passive"))
      (node (ref "C56") (pin "1") (pinfunction "1_1") (pintype "passive"))
      (node (ref "C58") (pin "1") (pinfunction "1_1") (pintype "passive"))
      (node (ref "C6") (pin "1") (pinfunction "1_1") (pintype "passive"))
      (node (ref "C7") (pin "1") (pinfunction "1_1") (pintype "passive"))
      (node (ref "C8") (pin "1") (pinfunction "1_1") (pintype "passive"))
      (node (ref "C9") (pin "1") (pinfunction "1_1") (pintype "passive"))
      (node (ref "D1") (pin "1") (pinfunction "VDD_1") (pintype "bidirectional"))
      (node (ref "D10") (pin "1") (pinfunction "VDD_1") (pintype "bidirectional"))
      (node (ref "D11") (pin "1") (pinfunction "VDD_1") (pintype "bidirectional"))
      (node (ref "D12") (pin "1") (pinfunction "VDD_1") (pintype "bidirectional"))
      (node (ref "D13") (pin "1") (pinfunction "VDD_1") (pintype "bidirectional"))
      (node (ref "D14") (pin "1") (pinfunction "VDD_1") (pintype "bidirectional"))
      (node (ref "D15") (pin "1") (pinfunction "VDD_1") (pintype "bidirectional"))
      (node (ref "D16") (pin "1") (pinfunction "VDD_1") (pintype "bidirectional"))
      (node (ref "D17") (pin "1") (pinfunction "VDD_1") (pintype "bidirectional"))
      (node (ref "D18") (pin "1") (pinfunction "VDD_1") (pintype "bidirectional"))
      (node (ref "D19") (pin "1") (pinfunction "VDD_1") (pintype "bidirectional"))
      (node (ref "D2") (pin "1") (pinfunction "VDD_1") (pintype "bidirectional"))
      (node (ref "D20") (pin "1") (pinfunction "VDD_1") (pintype "bidirectional"))
      (node (ref "D21") (pin "1") (pinfunction "VDD_1") (pintype "bidirectional"))
      (node (ref "D22") (pin "1") (pinfunction "VDD_1") (pintype "bidirectional"))
      (node (ref "D23") (pin "1") (pinfunction "VDD_1") (pintype "bidirectional"))
      (node (ref "D24") (pin "1") (pinfunction "VDD_1") (pintype "bidirectional"))
      (node (ref "D25") (pin "1") (pinfunction "VDD_1") (pintype "bidirectional"))
      (node (ref "D26") (pin "1") (pinfunction "VDD_1") (pintype "bidirectional"))
      (node (ref "D27") (pin "1") (pinfunction "VDD_1") (pintype "bidirectional"))
      (node (ref "D28") (pin "1") (pinfunction "VDD_1") (pintype "bidirectional"))
      (node (ref "D29") (pin "1") (pinfunction "VDD_1") (pintype "bidirectional"))
      (node (ref "D3") (pin "1") (pinfunction "VDD_1") (pintype "bidirectional"))
      (node (ref "D30") (pin "1") (pinfunction "VDD_1") (pintype "bidirectional"))
      (node (ref "D31") (pin "1") (pinfunction "VDD_1") (pintype "bidirectional"))
      (node (ref "D32") (pin "1") (pinfunction "VDD_1") (pintype "bidirectional"))
      (node (ref "D33") (pin "1") (pinfunction "VDD_1") (pintype "bidirectional"))
      (node (ref "D34") (pin "1") (pinfunction "VDD_1") (pintype "bidirectional"))
      (node (ref "D35") (pin "1") (pinfunction "VDD_1") (pintype "bidirectional"))
      (node (ref "D36") (pin "1") (pinfunction "VDD_1") (pintype "bidirectional"))
      (node (ref "D37") (pin "1") (pinfunction "VDD_1") (pintype "bidirectional"))
      (node (ref "D38") (pin "1") (pinfunction "VDD_1") (pintype "bidirectional"))
      (node (ref "D39") (pin "1") (pinfunction "VDD_1") (pintype "bidirectional"))
      (node (ref "D4") (pin "1") (pinfunction "VDD_1") (pintype "bidirectional"))
      (node (ref "D40") (pin "1") (pinfunction "VDD_1") (pintype "bidirectional"))
      (node (ref "D41") (pin "1") (pinfunction "VDD_1") (pintype "bidirectional"))
      (node (ref "D42") (pin "1") (pinfunction "VDD_1") (pintype "bidirectional"))
      (node (ref "D43") (pin "1") (pinfunction "VDD_1") (pintype "bidirectional"))
      (node (ref "D44") (pin "1") (pinfunction "VDD_1") (pintype "bidirectional"))
      (node (ref "D45") (pin "1") (pinfunction "VDD_1") (pintype "bidirectional"))
      (node (ref "D46") (pin "1") (pinfunction "VDD_1") (pintype "bidirectional"))
      (node (ref "D47") (pin "1") (pinfunction "VDD_1") (pintype "bidirectional"))
      (node (ref "D48") (pin "1") (pinfunction "VDD_1") (pintype "bidirectional"))
      (node (ref "D49") (pin "1") (pinfunction "VDD_1") (pintype "bidirectional"))
      (node (ref "D5") (pin "1") (pinfunction "VDD_1") (pintype "bidirectional"))
      (node (ref "D50") (pin "1") (pinfunction "VDD_1") (pintype "bidirectional"))
      (node (ref "D51") (pin "1") (pinfunction "VDD_1") (pintype "bidirectional"))
      (node (ref "D52") (pin "1") (pinfunction "VDD_1") (pintype "bidirectional"))
      (node (ref "D53") (pin "1") (pinfunction "VDD_1") (pintype "bidirectional"))
      (node (ref "D54") (pin "1") (pinfunction "VDD_1") (pintype "bidirectional"))
      (node (ref "D55") (pin "1") (pinfunction "VDD_1") (pintype "bidirectional"))
      (node (ref "D56") (pin "1") (pinfunction "VDD_1") (pintype "bidirectional"))
      (node (ref "D57") (pin "1") (pinfunction "VDD_1") (pintype "bidirectional"))
      (node (ref "D58") (pin "1") (pinfunction "VDD_1") (pintype "bidirectional"))
      (node (ref "D59") (pin "1") (pinfunction "VDD_1") (pintype "bidirectional"))
      (node (ref "D6") (pin "1") (pinfunction "VDD_1") (pintype "bidirectional"))
      (node (ref "D60") (pin "1") (pinfunction "VDD_1") (pintype "bidirectional"))
      (node (ref "D7") (pin "1") (pinfunction "VDD_1") (pintype "bidirectional"))
      (node (ref "D8") (pin "1") (pinfunction "VDD_1") (pintype "bidirectional"))
      (node (ref "D9") (pin "1") (pinfunction "VDD_1") (pintype "bidirectional"))
      (node (ref "R25") (pin "1") (pinfunction "1_1") (pintype "passive"))
      (node (ref "U$13") (pin "C1") (pinfunction "C_C1") (pintype "bidirectional"))
      (node (ref "U$13") (pin "C2") (pinfunction "C_C2") (pintype "bidirectional"))
      (node (ref "U$3") (pin "CENTER") (pinfunction "CENTER_CENTER") (pintype "bidirectional"))
      (node (ref "U4") (pin "3") (pinfunction "IN_3") (pintype "bidirectional"))
      (node (ref "X3") (pin "2") (pinfunction "KL_2") (pintype "passive"))
    )
    (net (code "20") (name "/OPTO") (class "Default")
      (node (ref "IC2") (pin "4") (pinfunction "COL_4") (pintype "passive"))
      (node (ref "IC3") (pin "6") (pinfunction "GPIO4_6") (pintype "bidirectional"))
      (node (ref "R1") (pin "1") (pinfunction "1_1") (pintype "passive"))
    )
    (net (code "21") (name "/PROG") (class "Default")
      (node (ref "IC1") (pin "2") (pinfunction "PROG_2") (pintype "bidirectional"))
      (node (ref "R8") (pin "1") (pinfunction "1_1") (pintype "passive"))
    )
    (net (code "22") (name "/RELAY1") (class "Default")
      (node (ref "IC3") (pin "14") (pinfunction "GPIO12_14") (pintype "bidirectional"))
    )
    (net (code "23") (name "/RX") (class "Default")
      (node (ref "IC3") (pin "8") (pinfunction "TXD_8") (pintype "bidirectional"))
      (node (ref "RX") (pin "TP") (pinfunction "TP_TP") (pintype "input"))
    )
    (net (code "24") (name "/STATUSLED") (class "Default")
      (node (ref "IC3") (pin "15") (pinfunction "GPIO13_15") (pintype "bidirectional"))
    )
    (net (code "25") (name "/TX") (class "Default")
      (node (ref "IC3") (pin "7") (pinfunction "RXD_7") (pintype "bidirectional"))
      (node (ref "TX") (pin "TP") (pinfunction "TP_TP") (pintype "input"))
    )
    (net (code "26") (name "/VUSB") (class "Default")
      (node (ref "C64") (pin "1") (pinfunction "1_1") (pintype "passive"))
      (node (ref "D61") (pin "C") (pinfunction "C_C") (pintype "passive"))
      (node (ref "IC1") (pin "4") (pinfunction "VCC_4") (pintype "bidirectional"))
      (node (ref "IC1") (pin "8") (pinfunction "CE_8") (pintype "bidirectional"))
      (node (ref "LED1") (pin "A") (pinfunction "A_A") (pintype "passive"))
      (node (ref "LED2") (pin "A") (pinfunction "A_A") (pintype "passive"))
    )
    (net (code "27") (name "DIN1") (class "Default")
      (node (ref "D1") (pin "4") (pinfunction "DI_4") (pintype "bidirectional"))
      (node (ref "Q3") (pin "3") (pinfunction "D_3") (pintype "passive"))
      (node (ref "R1-IN") (pin "1") (pinfunction "P_1") (pintype "passive"))
      (node (ref "R25") (pin "2") (pinfunction "2_2") (pintype "passive"))
    )
    (net (code "28") (name "GND") (class "Default")
      (node (ref "C10") (pin "2") (pinfunction "2_2") (pintype "passive"))
      (node (ref "C11") (pin "2") (pinfunction "2_2") (pintype "passive"))
      (node (ref "C12") (pin "2") (pinfunction "2_2") (pintype "passive"))
      (node (ref "C13") (pin "1") (pinfunction "1_1") (pintype "passive"))
      (node (ref "C14") (pin "2") (pinfunction "2_2") (pintype "passive"))
      (node (ref "C15") (pin "2") (pinfunction "2_2") (pintype "passive"))
      (node (ref "C16") (pin "2") (pinfunction "2_2") (pintype "passive"))
      (node (ref "C17") (pin "2") (pinfunction "2_2") (pintype "passive"))
      (node (ref "C18") (pin "2") (pinfunction "2_2") (pintype "passive"))
      (node (ref "C19") (pin "2") (pinfunction "2_2") (pintype "passive"))
      (node (ref "C20") (pin "2") (pinfunction "2_2") (pintype "passive"))
      (node (ref "C21") (pin "2") (pinfunction "2_2") (pintype "passive"))
      (node (ref "C22") (pin "2") (pinfunction "2_2") (pintype "passive"))
      (node (ref "C23") (pin "1") (pinfunction "1_1") (pintype "passive"))
      (node (ref "C24") (pin "2") (pinfunction "2_2") (pintype "passive"))
      (node (ref "C25") (pin "2") (pinfunction "2_2") (pintype "passive"))
      (node (ref "C26") (pin "2") (pinfunction "2_2") (pintype "passive"))
      (node (ref "C27") (pin "2") (pinfunction "2_2") (pintype "passive"))
      (node (ref "C28") (pin "2") (pinfunction "2_2") (pintype "passive"))
      (node (ref "C29") (pin "2") (pinfunction "2_2") (pintype "passive"))
      (node (ref "C3") (pin "1") (pinfunction "1_1") (pintype "passive"))
      (node (ref "C30") (pin "2") (pinfunction "2_2") (pintype "passive"))
      (node (ref "C31") (pin "2") (pinfunction "2_2") (pintype "passive"))
      (node (ref "C32") (pin "2") (pinfunction "2_2") (pintype "passive"))
      (node (ref "C33") (pin "1") (pinfunction "1_1") (pintype "passive"))
      (node (ref "C34") (pin "2") (pinfunction "2_2") (pintype "passive"))
      (node (ref "C35") (pin "2") (pinfunction "2_2") (pintype "passive"))
      (node (ref "C36") (pin "2") (pinfunction "2_2") (pintype "passive"))
      (node (ref "C37") (pin "2") (pinfunction "2_2") (pintype "passive"))
      (node (ref "C38") (pin "2") (pinfunction "2_2") (pintype "passive"))
      (node (ref "C39") (pin "2") (pinfunction "2_2") (pintype "passive"))
      (node (ref "C4") (pin "2") (pinfunction "2_2") (pintype "passive"))
      (node (ref "C40") (pin "2") (pinfunction "2_2") (pintype "passive"))
      (node (ref "C41") (pin "2") (pinfunction "2_2") (pintype "passive"))
      (node (ref "C42") (pin "2") (pinfunction "2_2") (pintype "passive"))
      (node (ref "C43") (pin "1") (pinfunction "1_1") (pintype "passive"))
      (node (ref "C44") (pin "2") (pinfunction "2_2") (pintype "passive"))
      (node (ref "C45") (pin "2") (pinfunction "2_2") (pintype "passive"))
      (node (ref "C46") (pin "2") (pinfunction "2_2") (pintype "passive"))
      (node (ref "C47") (pin "2") (pinfunction "2_2") (pintype "passive"))
      (node (ref "C48") (pin "2") (pinfunction "2_2") (pintype "passive"))
      (node (ref "C49") (pin "2") (pinfunction "2_2") (pintype "passive"))
      (node (ref "C5") (pin "2") (pinfunction "2_2") (pintype "passive"))
      (node (ref "C50") (pin "2") (pinfunction "2_2") (pintype "passive"))
      (node (ref "C51") (pin "2") (pinfunction "2_2") (pintype "passive"))
      (node (ref "C52") (pin "2") (pinfunction "2_2") (pintype "passive"))
      (node (ref "C53") (pin "1") (pinfunction "1_1") (pintype "passive"))
      (node (ref "C54") (pin "2") (pinfunction "2_2") (pintype "passive"))
      (node (ref "C55") (pin "2") (pinfunction "2_2") (pintype "passive"))
      (node (ref "C56") (pin "2") (pinfunction "2_2") (pintype "passive"))
      (node (ref "C57") (pin "2") (pinfunction "2_2") (pintype "passive"))
      (node (ref "C58") (pin "2") (pinfunction "2_2") (pintype "passive"))
      (node (ref "C59") (pin "2") (pinfunction "2_2") (pintype "passive"))
      (node (ref "C6") (pin "2") (pinfunction "2_2") (pintype "passive"))
      (node (ref "C60") (pin "1") (pinfunction "1_1") (pintype "passive"))
      (node (ref "C62") (pin "-") (pinfunction "-_-") (pintype "passive"))
      (node (ref "C63") (pin "-") (pinfunction "-_-") (pintype "passive"))
      (node (ref "C64") (pin "2") (pinfunction "2_2") (pintype "passive"))
      (node (ref "C7") (pin "2") (pinfunction "2_2") (pintype "passive"))
      (node (ref "C8") (pin "2") (pinfunction "2_2") (pintype "passive"))
      (node (ref "C9") (pin "2") (pinfunction "2_2") (pintype "passive"))
      (node (ref "D1") (pin "3") (pinfunction "VSS_3") (pintype "bidirectional"))
      (node (ref "D10") (pin "3") (pinfunction "VSS_3") (pintype "bidirectional"))
      (node (ref "D11") (pin "3") (pinfunction "VSS_3") (pintype "bidirectional"))
      (node (ref "D12") (pin "3") (pinfunction "VSS_3") (pintype "bidirectional"))
      (node (ref "D13") (pin "3") (pinfunction "VSS_3") (pintype "bidirectional"))
      (node (ref "D14") (pin "3") (pinfunction "VSS_3") (pintype "bidirectional"))
      (node (ref "D15") (pin "3") (pinfunction "VSS_3") (pintype "bidirectional"))
      (node (ref "D16") (pin "3") (pinfunction "VSS_3") (pintype "bidirectional"))
      (node (ref "D17") (pin "3") (pinfunction "VSS_3") (pintype "bidirectional"))
      (node (ref "D18") (pin "3") (pinfunction "VSS_3") (pintype "bidirectional"))
      (node (ref "D19") (pin "3") (pinfunction "VSS_3") (pintype "bidirectional"))
      (node (ref "D2") (pin "3") (pinfunction "VSS_3") (pintype "bidirectional"))
      (node (ref "D20") (pin "3") (pinfunction "VSS_3") (pintype "bidirectional"))
      (node (ref "D21") (pin "3") (pinfunction "VSS_3") (pintype "bidirectional"))
      (node (ref "D22") (pin "3") (pinfunction "VSS_3") (pintype "bidirectional"))
      (node (ref "D23") (pin "3") (pinfunction "VSS_3") (pintype "bidirectional"))
      (node (ref "D24") (pin "3") (pinfunction "VSS_3") (pintype "bidirectional"))
      (node (ref "D25") (pin "3") (pinfunction "VSS_3") (pintype "bidirectional"))
      (node (ref "D26") (pin "3") (pinfunction "VSS_3") (pintype "bidirectional"))
      (node (ref "D27") (pin "3") (pinfunction "VSS_3") (pintype "bidirectional"))
      (node (ref "D28") (pin "3") (pinfunction "VSS_3") (pintype "bidirectional"))
      (node (ref "D29") (pin "3") (pinfunction "VSS_3") (pintype "bidirectional"))
      (node (ref "D3") (pin "3") (pinfunction "VSS_3") (pintype "bidirectional"))
      (node (ref "D30") (pin "3") (pinfunction "VSS_3") (pintype "bidirectional"))
      (node (ref "D31") (pin "3") (pinfunction "VSS_3") (pintype "bidirectional"))
      (node (ref "D32") (pin "3") (pinfunction "VSS_3") (pintype "bidirectional"))
      (node (ref "D33") (pin "3") (pinfunction "VSS_3") (pintype "bidirectional"))
      (node (ref "D34") (pin "3") (pinfunction "VSS_3") (pintype "bidirectional"))
      (node (ref "D35") (pin "3") (pinfunction "VSS_3") (pintype "bidirectional"))
      (node (ref "D36") (pin "3") (pinfunction "VSS_3") (pintype "bidirectional"))
      (node (ref "D37") (pin "3") (pinfunction "VSS_3") (pintype "bidirectional"))
      (node (ref "D38") (pin "3") (pinfunction "VSS_3") (pintype "bidirectional"))
      (node (ref "D39") (pin "3") (pinfunction "VSS_3") (pintype "bidirectional"))
      (node (ref "D4") (pin "3") (pinfunction "VSS_3") (pintype "bidirectional"))
      (node (ref "D40") (pin "3") (pinfunction "VSS_3") (pintype "bidirectional"))
      (node (ref "D41") (pin "3") (pinfunction "VSS_3") (pintype "bidirectional"))
      (node (ref "D42") (pin "3") (pinfunction "VSS_3") (pintype "bidirectional"))
      (node (ref "D43") (pin "3") (pinfunction "VSS_3") (pintype "bidirectional"))
      (node (ref "D44") (pin "3") (pinfunction "VSS_3") (pintype "bidirectional"))
      (node (ref "D45") (pin "3") (pinfunction "VSS_3") (pintype "bidirectional"))
      (node (ref "D46") (pin "3") (pinfunction "VSS_3") (pintype "bidirectional"))
      (node (ref "D47") (pin "3") (pinfunction "VSS_3") (pintype "bidirectional"))
      (node (ref "D48") (pin "3") (pinfunction "VSS_3") (pintype "bidirectional"))
      (node (ref "D49") (pin "3") (pinfunction "VSS_3") (pintype "bidirectional"))
      (node (ref "D5") (pin "3") (pinfunction "VSS_3") (pintype "bidirectional"))
      (node (ref "D50") (pin "3") (pinfunction "VSS_3") (pintype "bidirectional"))
      (node (ref "D51") (pin "3") (pinfunction "VSS_3") (pintype "bidirectional"))
      (node (ref "D52") (pin "3") (pinfunction "VSS_3") (pintype "bidirectional"))
      (node (ref "D53") (pin "3") (pinfunction "VSS_3") (pintype "bidirectional"))
      (node (ref "D54") (pin "3") (pinfunction "VSS_3") (pintype "bidirectional"))
      (node (ref "D55") (pin "3") (pinfunction "VSS_3") (pintype "bidirectional"))
      (node (ref "D56") (pin "3") (pinfunction "VSS_3") (pintype "bidirectional"))
      (node (ref "D57") (pin "3") (pinfunction "VSS_3") (pintype "bidirectional"))
      (node (ref "D58") (pin "3") (pinfunction "VSS_3") (pintype "bidirectional"))
      (node (ref "D59") (pin "3") (pinfunction "VSS_3") (pintype "bidirectional"))
      (node (ref "D6") (pin "3") (pinfunction "VSS_3") (pintype "bidirectional"))
      (node (ref "D60") (pin "3") (pinfunction "VSS_3") (pintype "bidirectional"))
      (node (ref "D62") (pin "A") (pinfunction "A_A") (pintype "passive"))
      (node (ref "D63") (pin "A") (pinfunction "A_A") (pintype "passive"))
      (node (ref "D7") (pin "3") (pinfunction "VSS_3") (pintype "bidirectional"))
      (node (ref "D8") (pin "3") (pinfunction "VSS_3") (pintype "bidirectional"))
      (node (ref "D9") (pin "3") (pinfunction "VSS_3") (pintype "bidirectional"))
      (node (ref "GND") (pin "TP") (pinfunction "TP_TP") (pintype "input"))
      (node (ref "IC1") (pin "1") (pinfunction "TEMP_1") (pintype "bidirectional"))
      (node (ref "IC1") (pin "3") (pinfunction "GND_3") (pintype "bidirectional"))
      (node (ref "IC2") (pin "2") (pinfunction "C_2") (pintype "passive"))
      (node (ref "IC2") (pin "3") (pinfunction "EMIT_3") (pintype "passive"))
      (node (ref "IC3") (pin "1") (pinfunction "GND_1") (pintype "bidirectional"))
      (node (ref "IC4") (pin "3") (pinfunction "GND_3") (pintype "power_in"))
      (node (ref "IC4") (pin "5") (pinfunction "EN_5") (pintype "input"))
      (node (ref "IC4") (pin "6") (pinfunction "GND_6") (pintype "power_in"))
      (node (ref "MODE0") (pin "2") (pinfunction "2_2") (pintype "passive"))
      (node (ref "R12") (pin "1") (pinfunction "1_1") (pintype "passive"))
      (node (ref "R2") (pin "1") (pinfunction "1_1") (pintype "passive"))
      (node (ref "R7") (pin "1") (pinfunction "1_1") (pintype "passive"))
      (node (ref "R8") (pin "2") (pinfunction "2_2") (pintype "passive"))
      (node (ref "RESET") (pin "2") (pinfunction "2_2") (pintype "passive"))
      (node (ref "U$13") (pin "COIL+") (pinfunction "COIL=_COIL+") (pintype "bidirectional"))
      (node (ref "U$2") (pin "3") (pinfunction "S2_3") (pintype "bidirectional"))
      (node (ref "U4") (pin "1") (pinfunction "GND_1") (pintype "bidirectional"))
      (node (ref "X2") (pin "1") (pinfunction "KL_1") (pintype "passive"))
      (node (ref "X3") (pin "1") (pinfunction "KL_1") (pintype "passive"))
    )
    (net (code "29") (name "IO0{slash}AUX1-INPUT") (class "Default")
      (node (ref "IC3") (pin "4") (pinfunction "GPIO0_4") (pintype "bidirectional"))
      (node (ref "MODE0") (pin "1") (pinfunction "1_1") (pintype "passive"))
      (node (ref "R3") (pin "2") (pinfunction "2_2") (pintype "passive"))
    )
    (net (code "30") (name "Net-(D1-DO)") (class "Default")
      (node (ref "D1") (pin "2") (pinfunction "DO_2") (pintype "bidirectional"))
      (node (ref "D2") (pin "4") (pinfunction "DI_4") (pintype "bidirectional"))
    )
    (net (code "31") (name "Net-(D2-DO)") (class "Default")
      (node (ref "D2") (pin "2") (pinfunction "DO_2") (pintype "bidirectional"))
      (node (ref "D3") (pin "4") (pinfunction "DI_4") (pintype "bidirectional"))
    )
    (net (code "32") (name "Net-(D3-DO)") (class "Default")
      (node (ref "D3") (pin "2") (pinfunction "DO_2") (pintype "bidirectional"))
      (node (ref "D4") (pin "4") (pinfunction "DI_4") (pintype "bidirectional"))
    )
    (net (code "33") (name "Net-(D4-DO)") (class "Default")
      (node (ref "D4") (pin "2") (pinfunction "DO_2") (pintype "bidirectional"))
      (node (ref "D5") (pin "4") (pinfunction "DI_4") (pintype "bidirectional"))
    )
    (net (code "34") (name "Net-(D5-DO)") (class "Default")
      (node (ref "D5") (pin "2") (pinfunction "DO_2") (pintype "bidirectional"))
      (node (ref "D6") (pin "4") (pinfunction "DI_4") (pintype "bidirectional"))
    )
    (net (code "35") (name "Net-(D6-DO)") (class "Default")
      (node (ref "D6") (pin "2") (pinfunction "DO_2") (pintype "bidirectional"))
      (node (ref "D7") (pin "4") (pinfunction "DI_4") (pintype "bidirectional"))
    )
    (net (code "36") (name "Net-(D7-DO)") (class "Default")
      (node (ref "D7") (pin "2") (pinfunction "DO_2") (pintype "bidirectional"))
      (node (ref "D8") (pin "4") (pinfunction "DI_4") (pintype "bidirectional"))
    )
    (net (code "37") (name "Net-(D8-DO)") (class "Default")
      (node (ref "D8") (pin "2") (pinfunction "DO_2") (pintype "bidirectional"))
      (node (ref "D9") (pin "4") (pinfunction "DI_4") (pintype "bidirectional"))
    )
    (net (code "38") (name "Net-(D10-DI)") (class "Default")
      (node (ref "D10") (pin "4") (pinfunction "DI_4") (pintype "bidirectional"))
      (node (ref "D9") (pin "2") (pinfunction "DO_2") (pintype "bidirectional"))
    )
    (net (code "39") (name "Net-(D11-DO)") (class "Default")
      (node (ref "D11") (pin "2") (pinfunction "DO_2") (pintype "bidirectional"))
      (node (ref "D12") (pin "4") (pinfunction "DI_4") (pintype "bidirectional"))
    )
    (net (code "40") (name "Net-(D12-DO)") (class "Default")
      (node (ref "D12") (pin "2") (pinfunction "DO_2") (pintype "bidirectional"))
      (node (ref "D13") (pin "4") (pinfunction "DI_4") (pintype "bidirectional"))
    )
    (net (code "41") (name "Net-(D13-DO)") (class "Default")
      (node (ref "D13") (pin "2") (pinfunction "DO_2") (pintype "bidirectional"))
      (node (ref "D14") (pin "4") (pinfunction "DI_4") (pintype "bidirectional"))
    )
    (net (code "42") (name "Net-(D14-DO)") (class "Default")
      (node (ref "D14") (pin "2") (pinfunction "DO_2") (pintype "bidirectional"))
      (node (ref "D15") (pin "4") (pinfunction "DI_4") (pintype "bidirectional"))
    )
    (net (code "43") (name "Net-(D15-DO)") (class "Default")
      (node (ref "D15") (pin "2") (pinfunction "DO_2") (pintype "bidirectional"))
      (node (ref "D16") (pin "4") (pinfunction "DI_4") (pintype "bidirectional"))
    )
    (net (code "44") (name "Net-(D16-DO)") (class "Default")
      (node (ref "D16") (pin "2") (pinfunction "DO_2") (pintype "bidirectional"))
      (node (ref "D17") (pin "4") (pinfunction "DI_4") (pintype "bidirectional"))
    )
    (net (code "45") (name "Net-(D17-DO)") (class "Default")
      (node (ref "D17") (pin "2") (pinfunction "DO_2") (pintype "bidirectional"))
      (node (ref "D18") (pin "4") (pinfunction "DI_4") (pintype "bidirectional"))
    )
    (net (code "46") (name "Net-(D18-DO)") (class "Default")
      (node (ref "D18") (pin "2") (pinfunction "DO_2") (pintype "bidirectional"))
      (node (ref "D19") (pin "4") (pinfunction "DI_4") (pintype "bidirectional"))
    )
    (net (code "47") (name "Net-(D19-DO)") (class "Default")
      (node (ref "D19") (pin "2") (pinfunction "DO_2") (pintype "bidirectional"))
      (node (ref "D20") (pin "4") (pinfunction "DI_4") (pintype "bidirectional"))
    )
    (net (code "48") (name "Net-(D21-DO)") (class "Default")
      (node (ref "D21") (pin "2") (pinfunction "DO_2") (pintype "bidirectional"))
      (node (ref "D22") (pin "4") (pinfunction "DI_4") (pintype "bidirectional"))
    )
    (net (code "49") (name "Net-(D22-DO)") (class "Default")
      (node (ref "D22") (pin "2") (pinfunction "DO_2") (pintype "bidirectional"))
      (node (ref "D23") (pin "4") (pinfunction "DI_4") (pintype "bidirectional"))
    )
    (net (code "50") (name "Net-(D23-DO)") (class "Default")
      (node (ref "D23") (pin "2") (pinfunction "DO_2") (pintype "bidirectional"))
      (node (ref "D24") (pin "4") (pinfunction "DI_4") (pintype "bidirectional"))
    )
    (net (code "51") (name "Net-(D24-DO)") (class "Default")
      (node (ref "D24") (pin "2") (pinfunction "DO_2") (pintype "bidirectional"))
      (node (ref "D25") (pin "4") (pinfunction "DI_4") (pintype "bidirectional"))
    )
    (net (code "52") (name "Net-(D25-DO)") (class "Default")
      (node (ref "D25") (pin "2") (pinfunction "DO_2") (pintype "bidirectional"))
      (node (ref "D26") (pin "4") (pinfunction "DI_4") (pintype "bidirectional"))
    )
    (net (code "53") (name "Net-(D26-DO)") (class "Default")
      (node (ref "D26") (pin "2") (pinfunction "DO_2") (pintype "bidirectional"))
      (node (ref "D27") (pin "4") (pinfunction "DI_4") (pintype "bidirectional"))
    )
    (net (code "54") (name "Net-(D27-DO)") (class "Default")
      (node (ref "D27") (pin "2") (pinfunction "DO_2") (pintype "bidirectional"))
      (node (ref "D28") (pin "4") (pinfunction "DI_4") (pintype "bidirectional"))
    )
    (net (code "55") (name "Net-(D28-DO)") (class "Default")
      (node (ref "D28") (pin "2") (pinfunction "DO_2") (pintype "bidirectional"))
      (node (ref "D29") (pin "4") (pinfunction "DI_4") (pintype "bidirectional"))
    )
    (net (code "56") (name "Net-(D29-DO)") (class "Default")
      (node (ref "D29") (pin "2") (pinfunction "DO_2") (pintype "bidirectional"))
      (node (ref "D30") (pin "4") (pinfunction "DI_4") (pintype "bidirectional"))
    )
    (net (code "57") (name "Net-(D31-DO)") (class "Default")
      (node (ref "D31") (pin "2") (pinfunction "DO_2") (pintype "bidirectional"))
      (node (ref "D32") (pin "4") (pinfunction "DI_4") (pintype "bidirectional"))
    )
    (net (code "58") (name "Net-(D32-DO)") (class "Default")
      (node (ref "D32") (pin "2") (pinfunction "DO_2") (pintype "bidirectional"))
      (node (ref "D33") (pin "4") (pinfunction "DI_4") (pintype "bidirectional"))
    )
    (net (code "59") (name "Net-(D33-DO)") (class "Default")
      (node (ref "D33") (pin "2") (pinfunction "DO_2") (pintype "bidirectional"))
      (node (ref "D34") (pin "4") (pinfunction "DI_4") (pintype "bidirectional"))
    )
    (net (code "60") (name "Net-(D34-DO)") (class "Default")
      (node (ref "D34") (pin "2") (pinfunction "DO_2") (pintype "bidirectional"))
      (node (ref "D35") (pin "4") (pinfunction "DI_4") (pintype "bidirectional"))
    )
    (net (code "61") (name "Net-(D35-DO)") (class "Default")
      (node (ref "D35") (pin "2") (pinfunction "DO_2") (pintype "bidirectional"))
      (node (ref "D36") (pin "4") (pinfunction "DI_4") (pintype "bidirectional"))
    )
    (net (code "62") (name "Net-(D36-DO)") (class "Default")
      (node (ref "D36") (pin "2") (pinfunction "DO_2") (pintype "bidirectional"))
      (node (ref "D37") (pin "4") (pinfunction "DI_4") (pintype "bidirectional"))
    )
    (net (code "63") (name "Net-(D37-DO)") (class "Default")
      (node (ref "D37") (pin "2") (pinfunction "DO_2") (pintype "bidirectional"))
      (node (ref "D38") (pin "4") (pinfunction "DI_4") (pintype "bidirectional"))
    )
    (net (code "64") (name "Net-(D38-DO)") (class "Default")
      (node (ref "D38") (pin "2") (pinfunction "DO_2") (pintype "bidirectional"))
      (node (ref "D39") (pin "4") (pinfunction "DI_4") (pintype "bidirectional"))
    )
    (net (code "65") (name "Net-(D39-DO)") (class "Default")
      (node (ref "D39") (pin "2") (pinfunction "DO_2") (pintype "bidirectional"))
      (node (ref "D40") (pin "4") (pinfunction "DI_4") (pintype "bidirectional"))
    )
    (net (code "66") (name "Net-(D41-DO)") (class "Default")
      (node (ref "D41") (pin "2") (pinfunction "DO_2") (pintype "bidirectional"))
      (node (ref "D42") (pin "4") (pinfunction "DI_4") (pintype "bidirectional"))
    )
    (net (code "67") (name "Net-(D42-DO)") (class "Default")
      (node (ref "D42") (pin "2") (pinfunction "DO_2") (pintype "bidirectional"))
      (node (ref "D43") (pin "4") (pinfunction "DI_4") (pintype "bidirectional"))
    )
    (net (code "68") (name "Net-(D43-DO)") (class "Default")
      (node (ref "D43") (pin "2") (pinfunction "DO_2") (pintype "bidirectional"))
      (node (ref "D44") (pin "4") (pinfunction "DI_4") (pintype "bidirectional"))
    )
    (net (code "69") (name "Net-(D44-DO)") (class "Default")
      (node (ref "D44") (pin "2") (pinfunction "DO_2") (pintype "bidirectional"))
      (node (ref "D45") (pin "4") (pinfunction "DI_4") (pintype "bidirectional"))
    )
    (net (code "70") (name "Net-(D45-DO)") (class "Default")
      (node (ref "D45") (pin "2") (pinfunction "DO_2") (pintype "bidirectional"))
      (node (ref "D46") (pin "4") (pinfunction "DI_4") (pintype "bidirectional"))
    )
    (net (code "71") (name "Net-(D46-DO)") (class "Default")
      (node (ref "D46") (pin "2") (pinfunction "DO_2") (pintype "bidirectional"))
      (node (ref "D47") (pin "4") (pinfunction "DI_4") (pintype "bidirectional"))
    )
    (net (code "72") (name "Net-(D47-DO)") (class "Default")
      (node (ref "D47") (pin "2") (pinfunction "DO_2") (pintype "bidirectional"))
      (node (ref "D48") (pin "4") (pinfunction "DI_4") (pintype "bidirectional"))
    )
    (net (code "73") (name "Net-(D48-DO)") (class "Default")
      (node (ref "D48") (pin "2") (pinfunction "DO_2") (pintype "bidirectional"))
      (node (ref "D49") (pin "4") (pinfunction "DI_4") (pintype "bidirectional"))
    )
    (net (code "74") (name "Net-(D49-DO)") (class "Default")
      (node (ref "D49") (pin "2") (pinfunction "DO_2") (pintype "bidirectional"))
      (node (ref "D50") (pin "4") (pinfunction "DI_4") (pintype "bidirectional"))
    )
    (net (code "75") (name "Net-(D51-DO)") (class "Default")
      (node (ref "D51") (pin "2") (pinfunction "DO_2") (pintype "bidirectional"))
      (node (ref "D52") (pin "4") (pinfunction "DI_4") (pintype "bidirectional"))
    )
    (net (code "76") (name "Net-(D52-DO)") (class "Default")
      (node (ref "D52") (pin "2") (pinfunction "DO_2") (pintype "bidirectional"))
      (node (ref "D53") (pin "4") (pinfunction "DI_4") (pintype "bidirectional"))
    )
    (net (code "77") (name "Net-(D53-DO)") (class "Default")
      (node (ref "D53") (pin "2") (pinfunction "DO_2") (pintype "bidirectional"))
      (node (ref "D54") (pin "4") (pinfunction "DI_4") (pintype "bidirectional"))
    )
    (net (code "78") (name "Net-(D54-DO)") (class "Default")
      (node (ref "D54") (pin "2") (pinfunction "DO_2") (pintype "bidirectional"))
      (node (ref "D55") (pin "4") (pinfunction "DI_4") (pintype "bidirectional"))
    )
    (net (code "79") (name "Net-(D55-DO)") (class "Default")
      (node (ref "D55") (pin "2") (pinfunction "DO_2") (pintype "bidirectional"))
      (node (ref "D56") (pin "4") (pinfunction "DI_4") (pintype "bidirectional"))
    )
    (net (code "80") (name "Net-(D56-DO)") (class "Default")
      (node (ref "D56") (pin "2") (pinfunction "DO_2") (pintype "bidirectional"))
      (node (ref "D57") (pin "4") (pinfunction "DI_4") (pintype "bidirectional"))
    )
    (net (code "81") (name "Net-(D57-DO)") (class "Default")
      (node (ref "D57") (pin "2") (pinfunction "DO_2") (pintype "bidirectional"))
      (node (ref "D58") (pin "4") (pinfunction "DI_4") (pintype "bidirectional"))
    )
    (net (code "82") (name "Net-(D58-DO)") (class "Default")
      (node (ref "D58") (pin "2") (pinfunction "DO_2") (pintype "bidirectional"))
      (node (ref "D59") (pin "4") (pinfunction "DI_4") (pintype "bidirectional"))
    )
    (net (code "83") (name "Net-(D59-DO)") (class "Default")
      (node (ref "D59") (pin "2") (pinfunction "DO_2") (pintype "bidirectional"))
      (node (ref "D60") (pin "4") (pinfunction "DI_4") (pintype "bidirectional"))
    )
    (net (code "84") (name "Net-(IC1-CHRG)") (class "Default")
      (node (ref "IC1") (pin "7") (pinfunction "CHRG_7") (pintype "bidirectional"))
      (node (ref "R10") (pin "2") (pinfunction "2_2") (pintype "passive"))
    )
    (net (code "85") (name "Net-(IC1-STDBY)") (class "Default")
      (node (ref "IC1") (pin "6") (pinfunction "STDBY_6") (pintype "bidirectional"))
      (node (ref "R9") (pin "2") (pinfunction "2_2") (pintype "passive"))
    )
    (net (code "86") (name "Net-(IC2-A)") (class "Default")
      (node (ref "IC2") (pin "1") (pinfunction "A_1") (pintype "passive"))
      (node (ref "R5") (pin "1") (pinfunction "1_1") (pintype "passive"))
    )
    (net (code "87") (name "Net-(IC3-CH_PD)") (class "Default")
      (node (ref "IC3") (pin "11") (pinfunction "CH_PD_11") (pintype "bidirectional"))
      (node (ref "R11") (pin "1") (pinfunction "1_1") (pintype "passive"))
    )
    (net (code "88") (name "Net-(IC3-GPIO2)") (class "Default")
      (node (ref "2") (pin "TP") (pinfunction "TP_TP") (pintype "input"))
      (node (ref "IC3") (pin "3") (pinfunction "GPIO2_3") (pintype "bidirectional"))
      (node (ref "R2") (pin "2") (pinfunction "2_2") (pintype "passive"))
    )
    (net (code "89") (name "Net-(IC3-GPIO15)") (class "Default")
      (node (ref "IC3") (pin "2") (pinfunction "GPIO15_2") (pintype "bidirectional"))
      (node (ref "R12") (pin "2") (pinfunction "2_2") (pintype "passive"))
    )
    (net (code "90") (name "Net-(IC3-GPIO16)") (class "Default")
      (node (ref "IC3") (pin "12") (pinfunction "GPIO16_12") (pintype "bidirectional"))
      (node (ref "SJ6") (pin "1") (pinfunction "1_1") (pintype "passive"))
    )
    (net (code "91") (name "Net-(IC4-OUT)") (class "Default")
      (node (ref "D63") (pin "C") (pinfunction "C_C") (pintype "passive"))
      (node (ref "IC4") (pin "2") (pinfunction "OUT_2") (pintype "output"))
      (node (ref "L1") (pin "1") (pinfunction "1_1") (pintype "passive"))
    )
    (net (code "92") (name "Net-(LED1-C)") (class "Default")
      (node (ref "LED1") (pin "K") (pinfunction "C_K") (pintype "passive"))
      (node (ref "R10") (pin "1") (pinfunction "1_1") (pintype "passive"))
    )
    (net (code "93") (name "Net-(LED2-C)") (class "Default")
      (node (ref "LED2") (pin "K") (pinfunction "C_K") (pintype "passive"))
      (node (ref "R9") (pin "1") (pinfunction "1_1") (pintype "passive"))
    )
    (net (code "94") (name "Net-(R4-Pad1)") (class "Default")
      (node (ref "R4") (pin "1") (pinfunction "1_1") (pintype "passive"))
      (node (ref "SJ6") (pin "3") (pinfunction "3_3") (pintype "passive"))
    )
    (net (code "95") (name "Net-(U$1-CS)") (class "Default")
      (node (ref "R7") (pin "2") (pinfunction "2_2") (pintype "passive"))
      (node (ref "U$1") (pin "2") (pinfunction "CS_2") (pintype "bidirectional"))
    )
    (net (code "96") (name "Net-(U$1-OC)") (class "Default")
      (node (ref "U$1") (pin "3") (pinfunction "OC_3") (pintype "bidirectional"))
      (node (ref "U$2") (pin "4") (pinfunction "G2_4") (pintype "bidirectional"))
    )
    (net (code "97") (name "Net-(U$1-OD)") (class "Default")
      (node (ref "U$1") (pin "1") (pinfunction "OD_1") (pintype "bidirectional"))
      (node (ref "U$2") (pin "6") (pinfunction "G1_6") (pintype "bidirectional"))
    )
    (net (code "98") (name "Net-(U$1-VCC)") (class "Default")
      (node (ref "C61") (pin "2") (pinfunction "2_2") (pintype "passive"))
      (node (ref "R6") (pin "1") (pinfunction "1_1") (pintype "passive"))
      (node (ref "U$1") (pin "5") (pinfunction "VCC_5") (pintype "bidirectional"))
    )
    (net (code "99") (name "RESET") (class "Default")
      (node (ref "IC3") (pin "9") (pinfunction "REST_9") (pintype "bidirectional"))
      (node (ref "RESET") (pin "1") (pinfunction "1_1") (pintype "passive"))
      (node (ref "SJ6") (pin "2") (pinfunction "2_2") (pintype "passive"))
    )
    (net (code "100") (name "WS2812-SIG") (class "Default")
      (node (ref "IC3") (pin "13") (pinfunction "GPIO14_13") (pintype "bidirectional"))
      (node (ref "Q3") (pin "2") (pinfunction "S_2") (pintype "passive"))
      (node (ref "R23") (pin "2") (pinfunction "2_2") (pintype "passive"))
    )
    (net (code "101") (name "unconnected-(MODE0-Pad3)") (class "Default")
      (node (ref "MODE0") (pin "3") (pinfunction "3_3") (pintype "passive"))
    )
    (net (code "102") (name "unconnected-(MODE0-Pad4)") (class "Default")
      (node (ref "MODE0") (pin "4") (pinfunction "4_4") (pintype "passive"))
    )
    (net (code "103") (name "unconnected-(RESET-Pad3)") (class "Default")
      (node (ref "RESET") (pin "3") (pinfunction "3_3") (pintype "passive"))
    )
    (net (code "104") (name "unconnected-(RESET-Pad4)") (class "Default")
      (node (ref "RESET") (pin "4") (pinfunction "4_4") (pintype "passive"))
    )
    (net (code "105") (name "unconnected-(U$1-TD-Pad4)") (class "Default")
      (node (ref "U$1") (pin "4") (pinfunction "TD_4") (pintype "bidirectional"))
    )
    (net (code "106") (name "unconnected-(U$2-D12_1-Pad2)") (class "Default")
      (node (ref "U$2") (pin "2") (pinfunction "D12_1_2") (pintype "bidirectional"))
    )
    (net (code "107") (name "unconnected-(U$2-D12_2-Pad5)") (class "Default")
      (node (ref "U$2") (pin "5") (pinfunction "D12_2_5") (pintype "bidirectional"))
    )
  )
)
